# touch_glove_bullshit.net
KiCad netlist of a schematic drawn in EAGLE
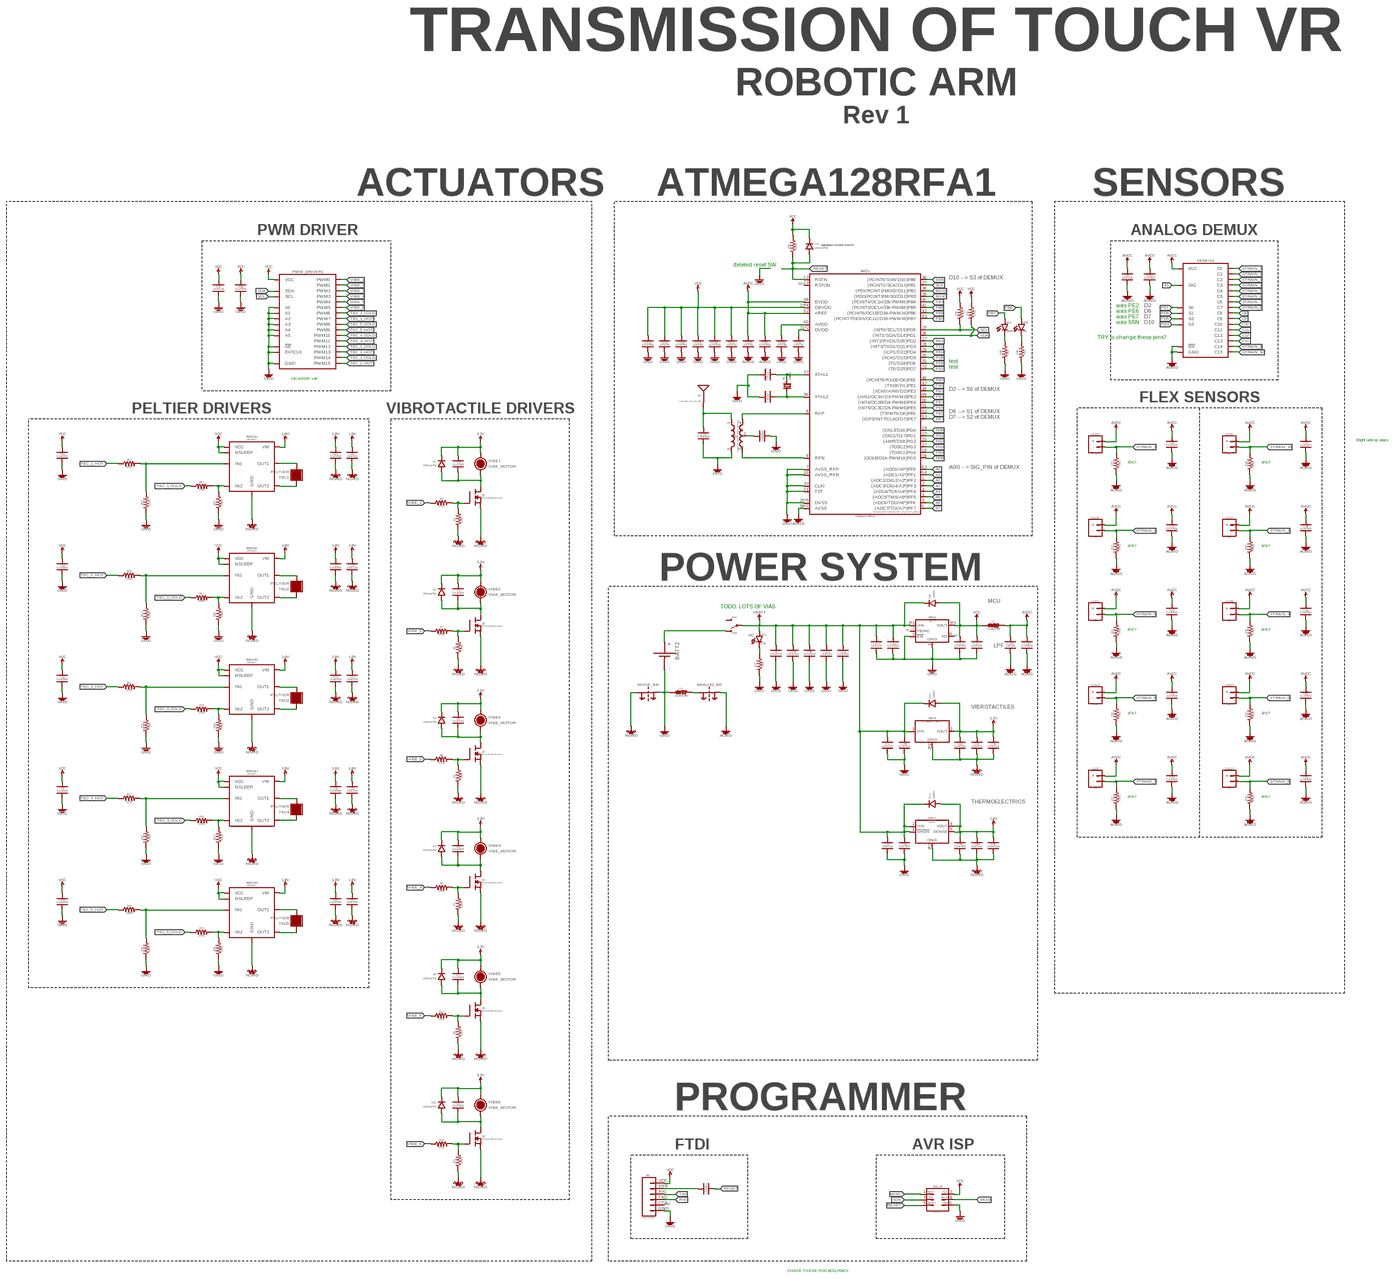
[diagram p0: schematic, sheet 1, overview]
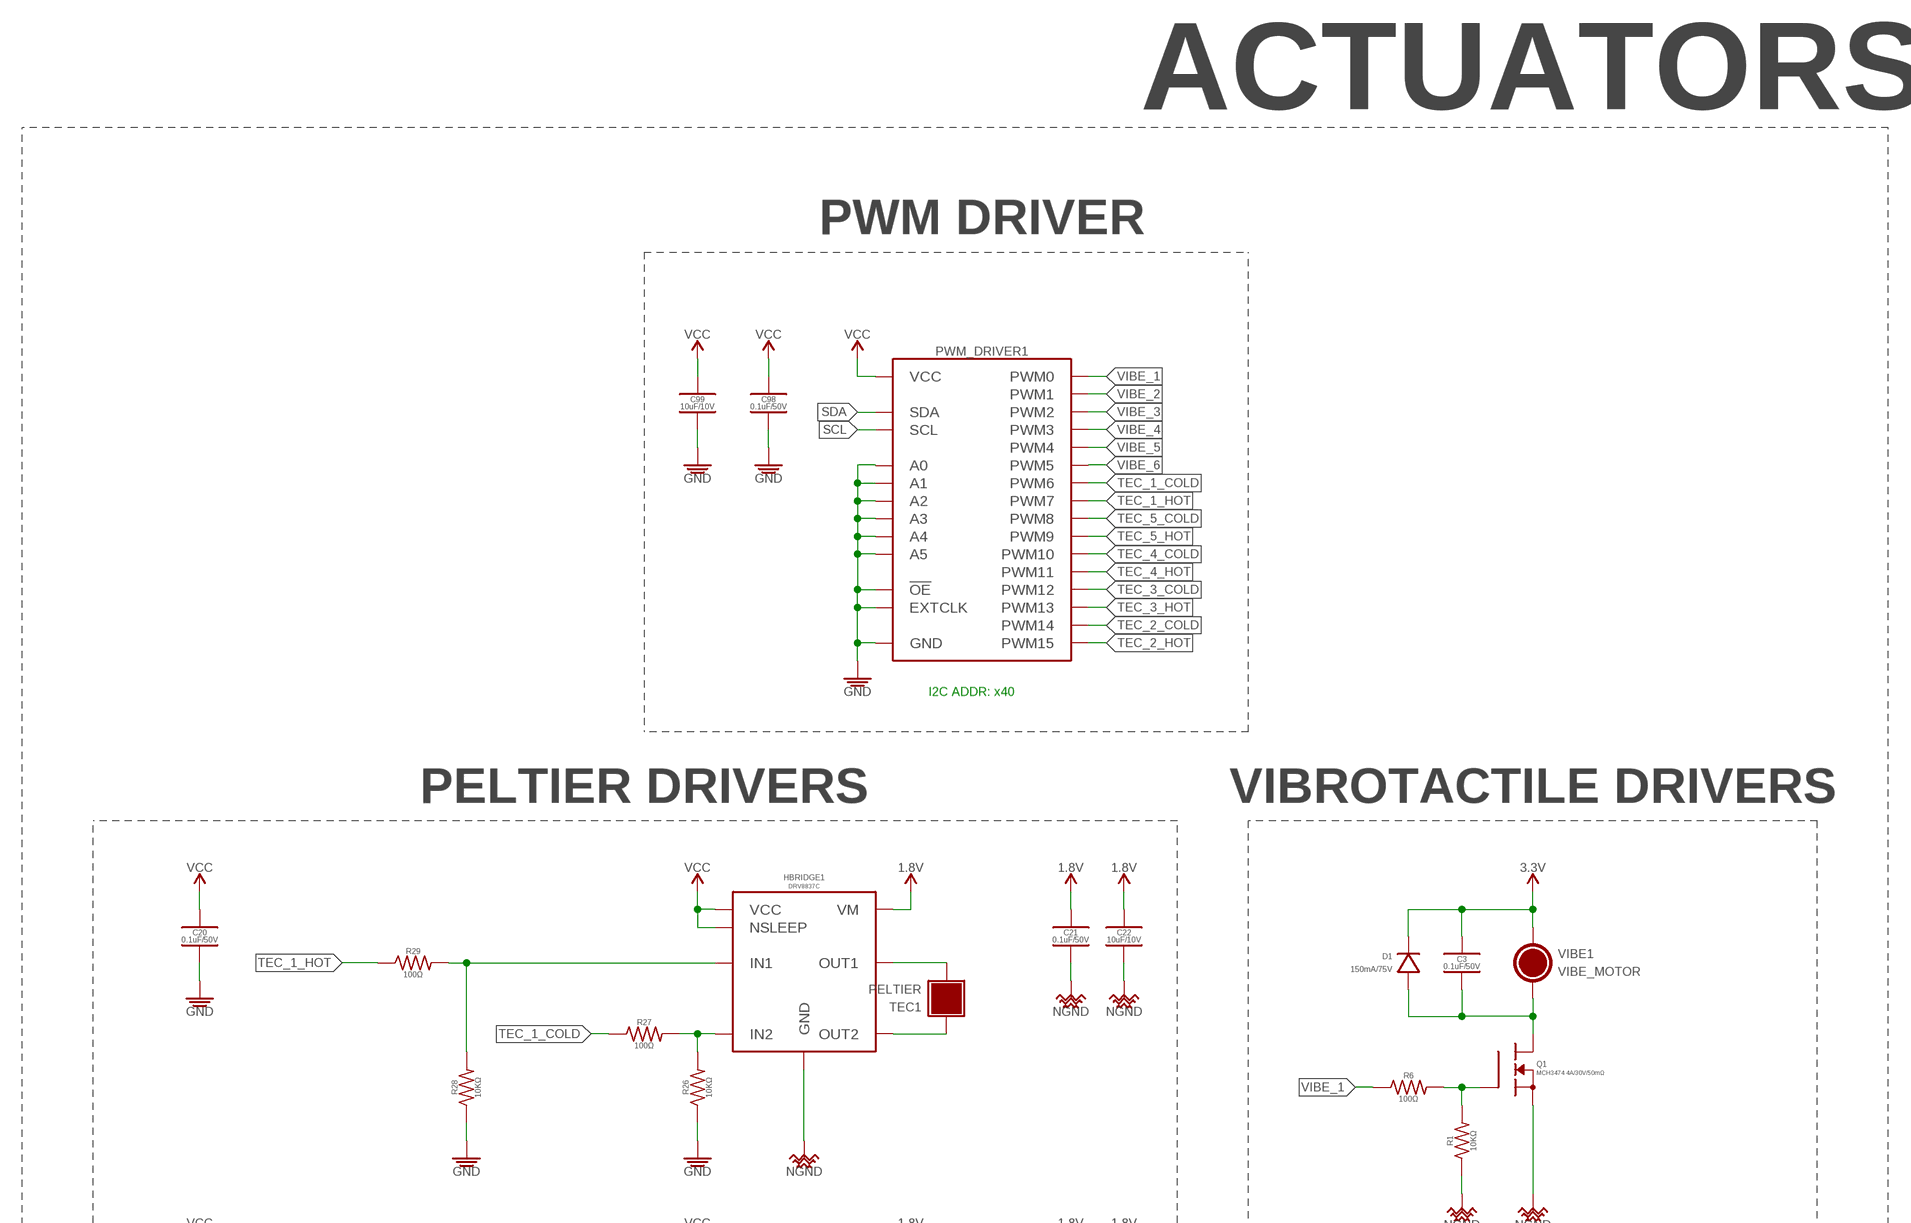
[diagram p1: schematic, sheet 1, part 1 of 4]
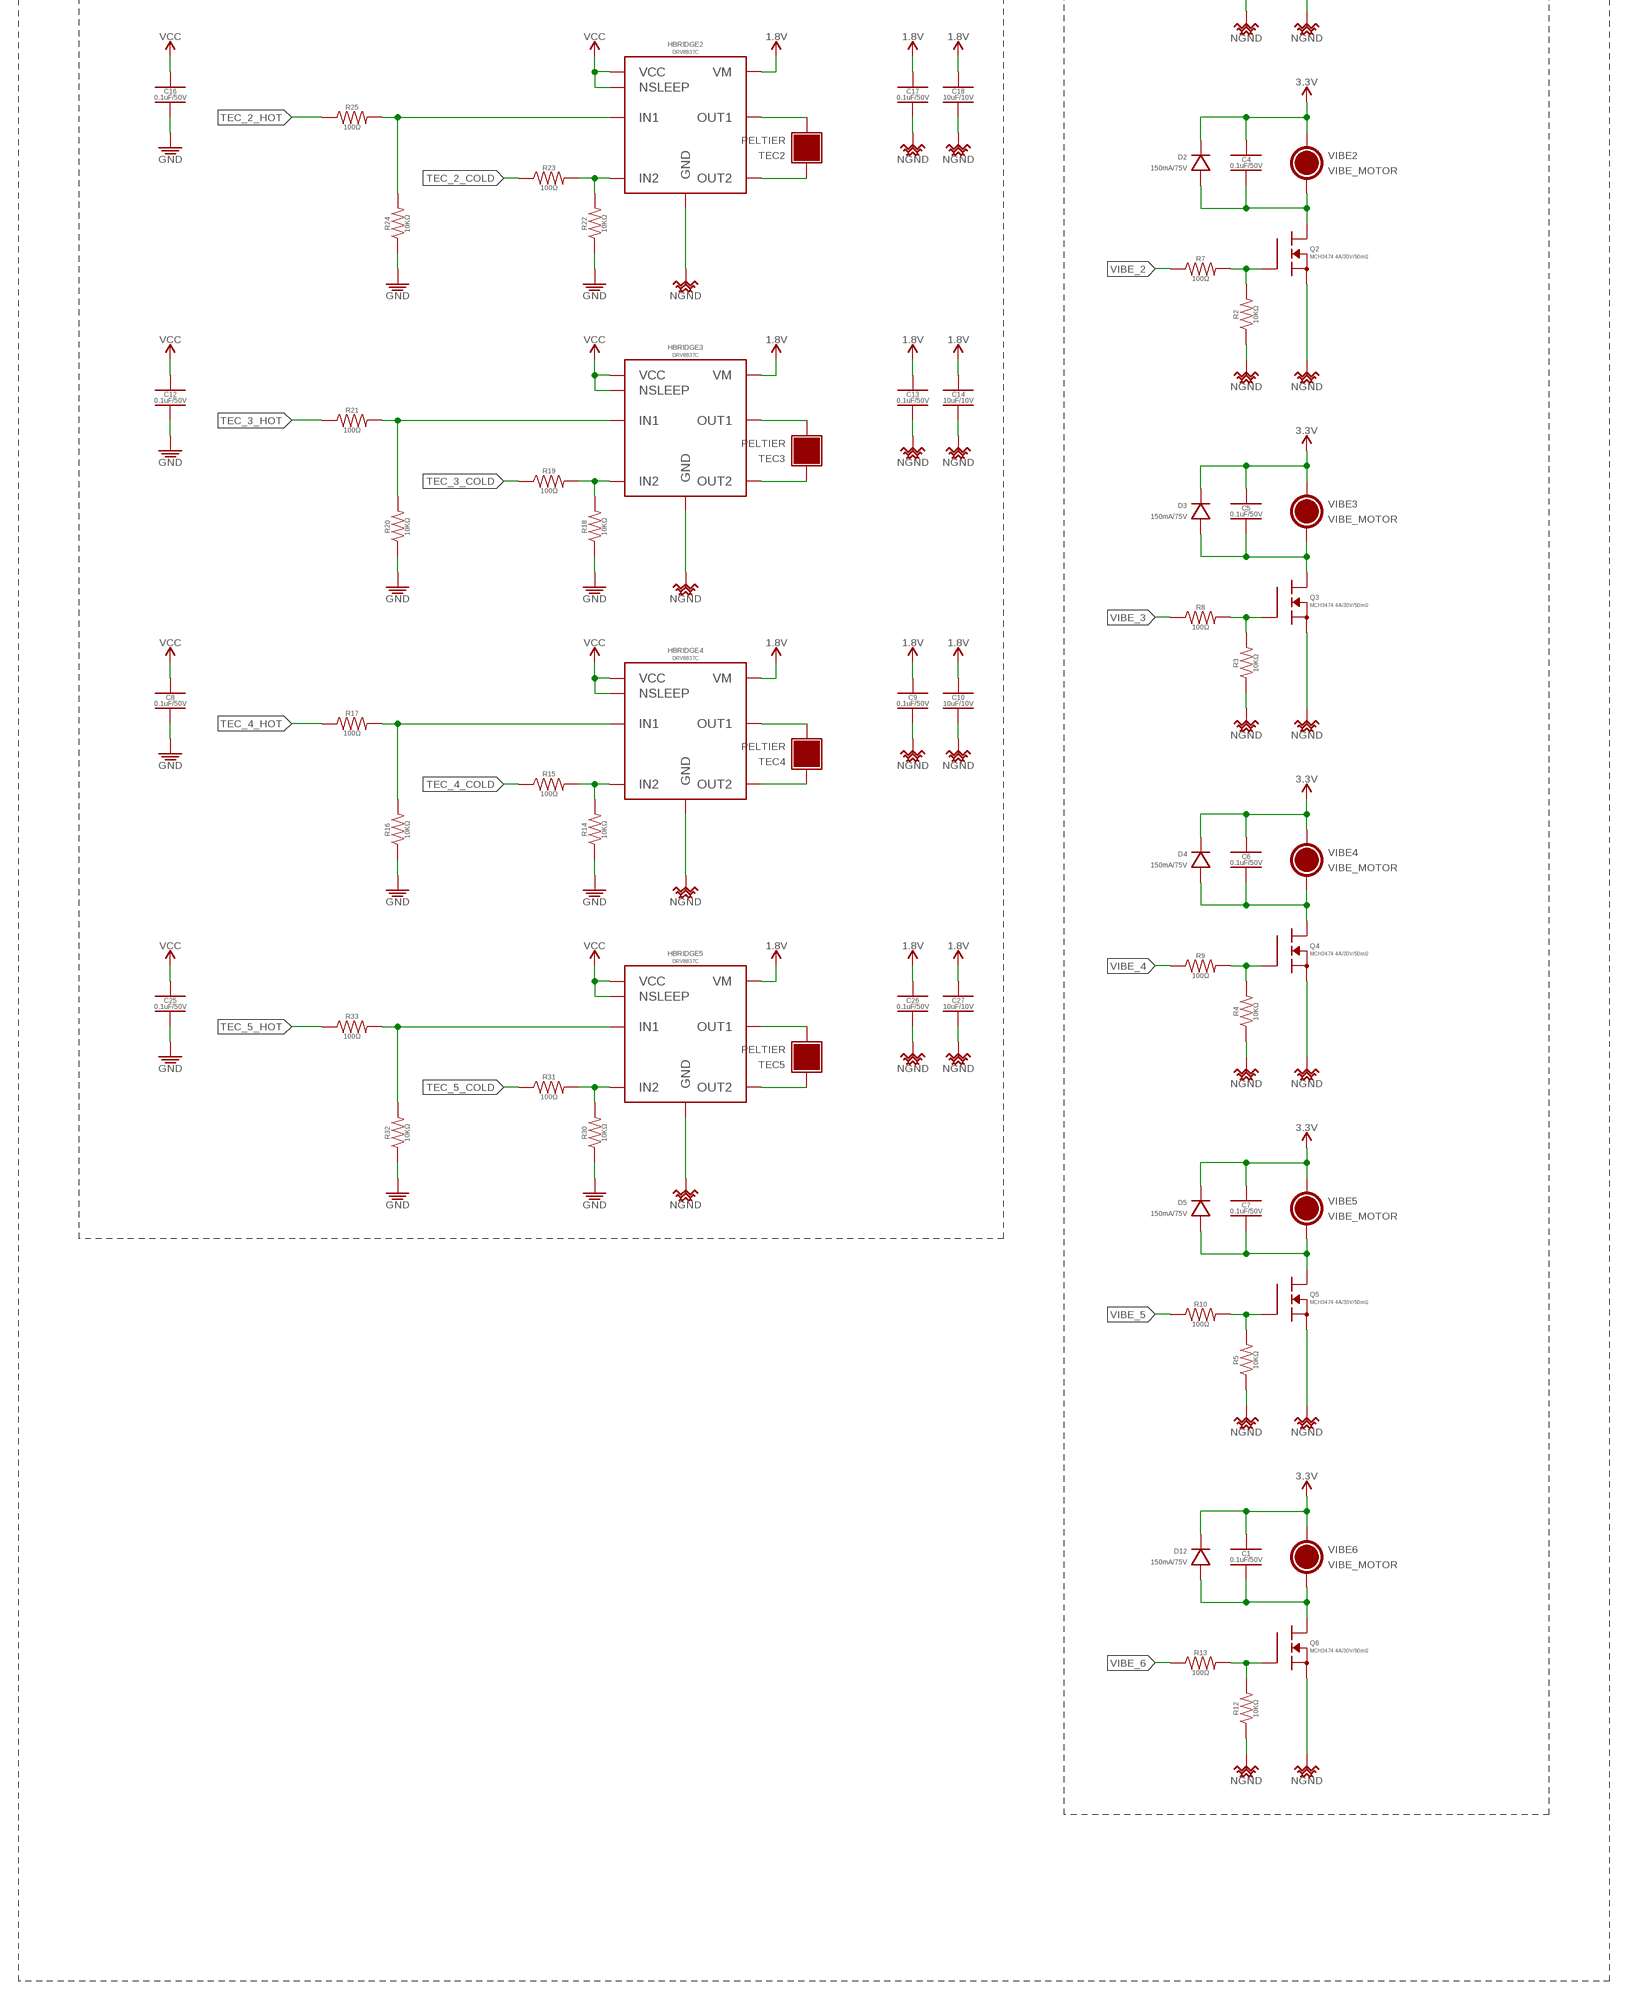
[diagram p2: schematic, sheet 1, part 2 of 4]
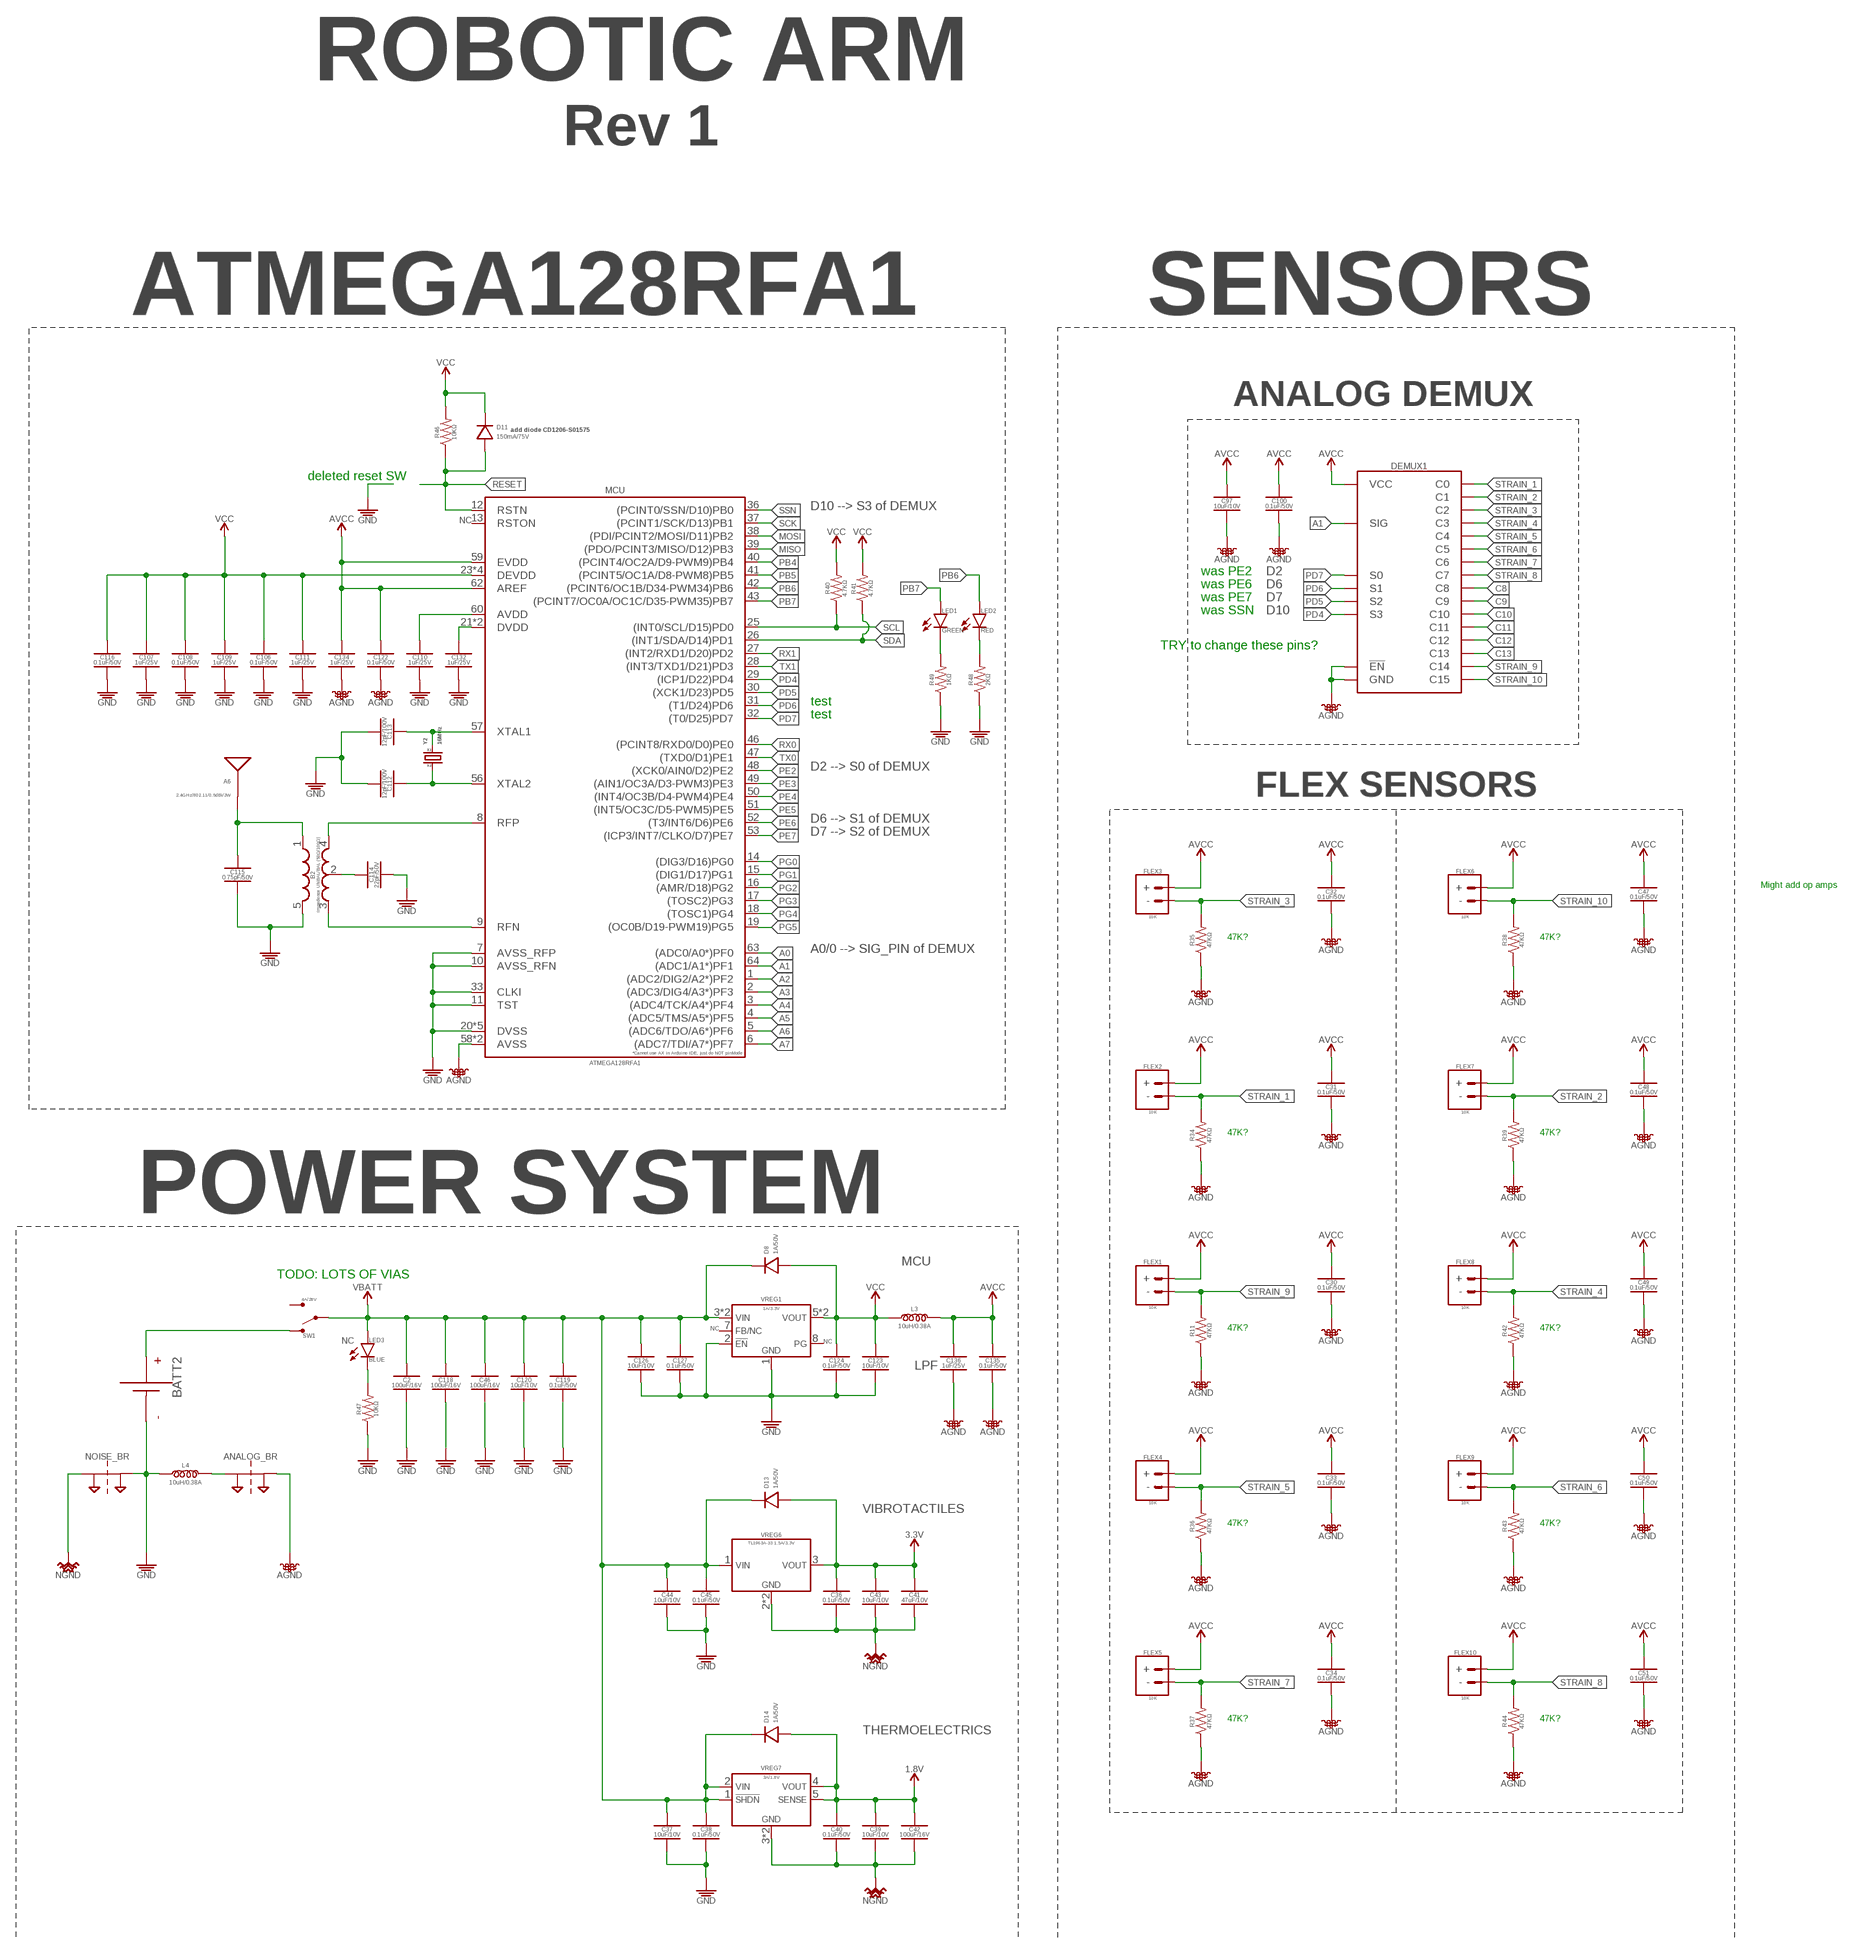
[diagram p3: schematic, sheet 1, part 3 of 4]
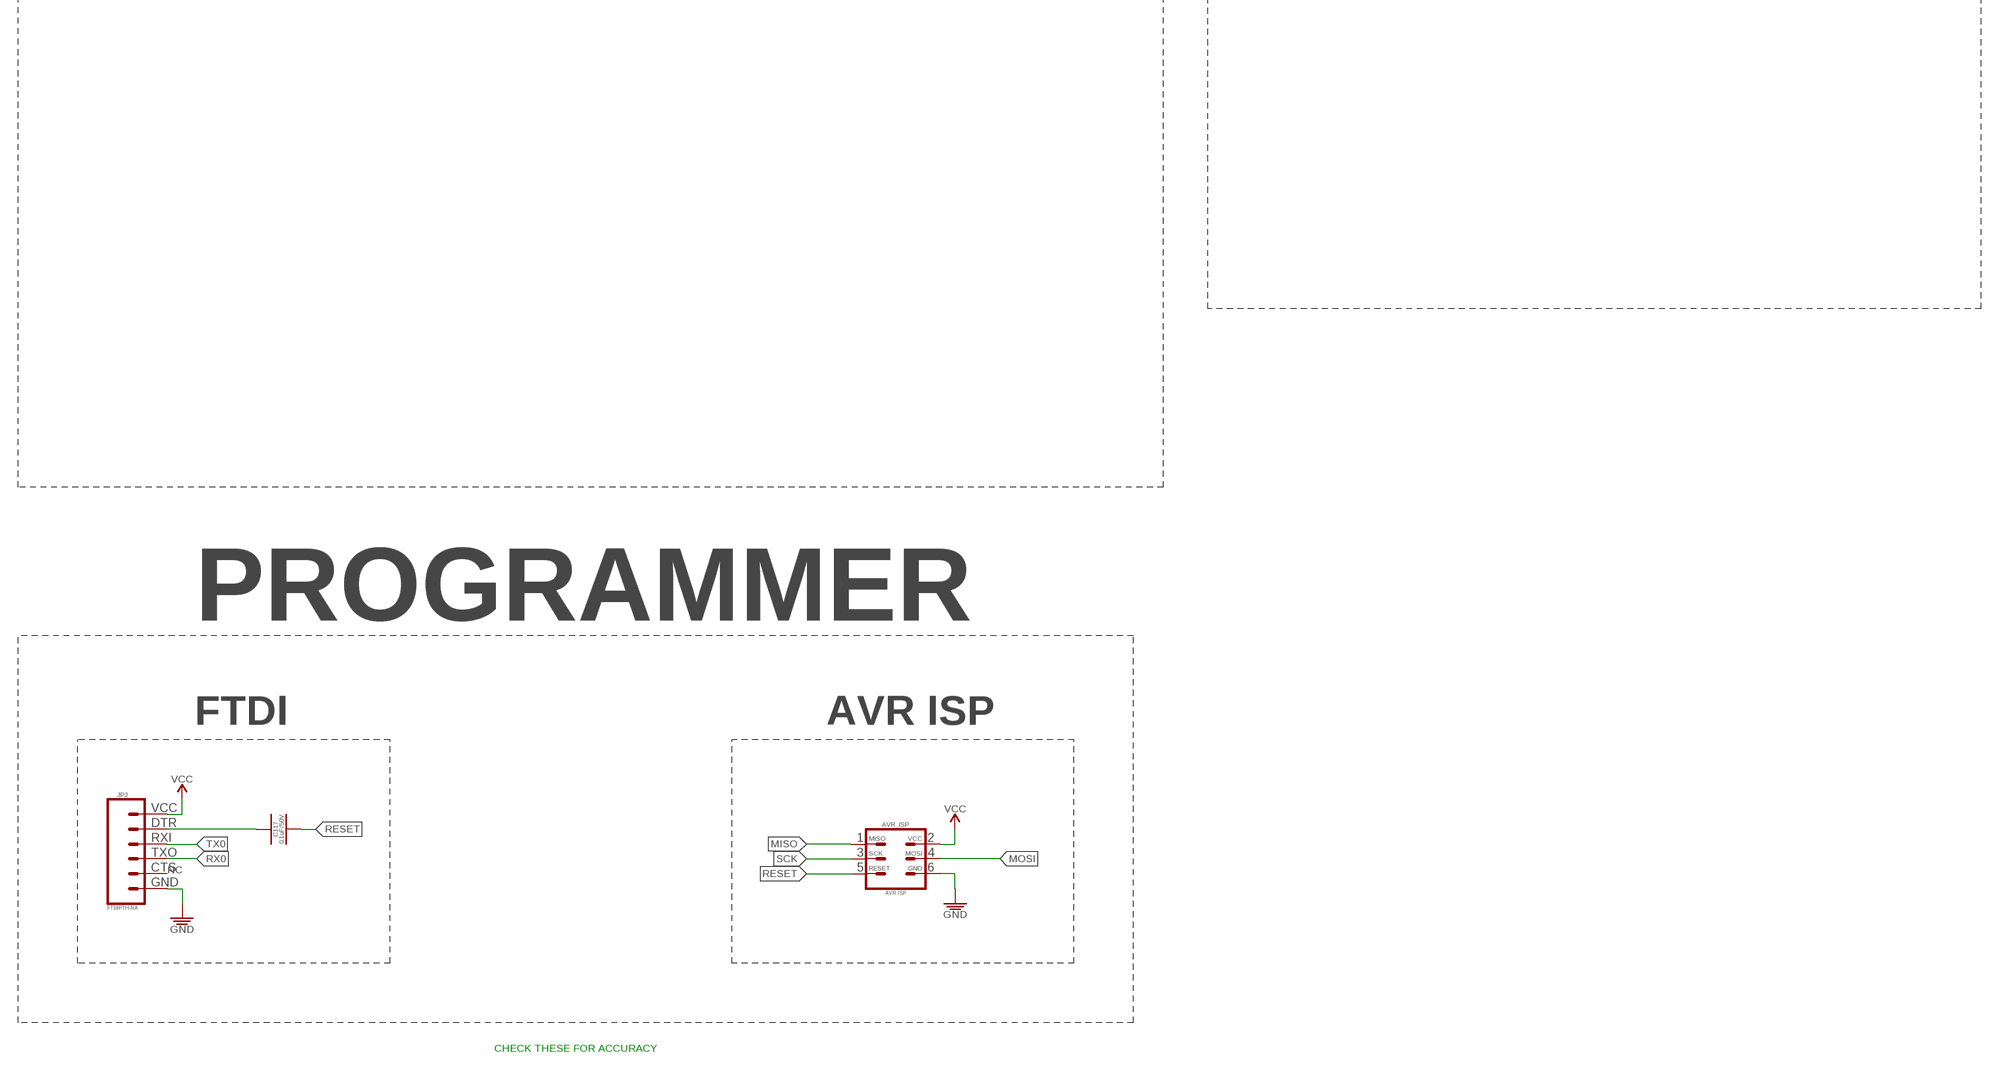
[diagram p4: schematic, sheet 1, part 4 of 4]

(export (version "E")
  (design (tool "Eeschema 10.0.6"))
  (components
    (comp (ref "A6")
      (value "2.4GHz/802.11/0.5dBi/3W")
      (footprint "eagle-import:ANTENNA-CHIP5")
      (fields
        (field (name "MFR") "Linx Technologies Inc.")
        (field (name "MPN") "ANT-2.45-CHP-T")
        (field (name "CREATOR") "Kenmei")
      )
      (libsource (lib "eagle-import") (part "ANTENNA_SMD-CHIP_2.4GHZ-0.5DBI-3W"))
    )
    (comp (ref "ANALOG_BR")
      (value "2PT_GND_TIE")
      (footprint "eagle-import:2PT_GND_TIE")
      (libsource (lib "eagle-import") (part "2PT_GND_TIE"))
    )
    (comp (ref "AVR_ISP")
      (value "AVR ISP")
      (footprint "eagle-import:2X3-NS")
      (fields (field (name "MFR") "Amphenol FCI") (field (name "MPN") "67997-206HLF"))
      (libsource (lib "eagle-import") (part "AVR_SPI_PRG_6NS"))
    )
    (comp (ref "B2")
      (value "Impedence UNBAL/BAL (50Ω/100Ω)")
      (footprint "eagle-import:0805_BALUN")
      (fields
        (field (name "MFR") "Wurth Electronics Inc")
        (field (name "MPN") "748421245")
        (field (name "CREATOR") "Kenmei")
      )
      (libsource (lib "eagle-import") (part "BALUN_SMD-0805_UNBAL/BAL-50/100"))
    )
    (comp (ref "BATT2")
      (value "BATTERYPTH_HOLES")
      (footprint "eagle-import:DUAL_PTH_PADS")
      (libsource (lib "eagle-import") (part "BATTERYPTH_HOLES"))
    )
    (comp (ref "C1")
      (value "0.1uF/50V")
      (footprint "eagle-import:_CER_SMD_0402")
      (fields
        (field (name "MFR") "Murata Electronics North America")
        (field (name "MPN") "GRM155R61H104KE19D")
        (field (name "CREATOR") "MrSwirlyEyes")
      )
      (libsource (lib "eagle-import") (part "0.1UF_SMD-0402_50V-10%"))
    )
    (comp (ref "C2")
      (value "100uF/16V")
      (footprint "eagle-import:_CER_SMD-1210")
      (fields
        (field (name "MFR") "Taiyo Yuden")
        (field (name "MPN") "EMK325ABJ107MM-T")
        (field (name "CREATOR") "MrSwirlyEyes")
      )
      (libsource (lib "eagle-import") (part "100UF_CER_SMD-1210_16V-20%"))
    )
    (comp (ref "C3")
      (value "0.1uF/50V")
      (footprint "eagle-import:_CER_SMD_0402")
      (fields
        (field (name "MFR") "Murata Electronics North America")
        (field (name "MPN") "GRM155R61H104KE19D")
        (field (name "CREATOR") "MrSwirlyEyes")
      )
      (libsource (lib "eagle-import") (part "0.1UF_SMD-0402_50V-10%"))
    )
    (comp (ref "C4")
      (value "0.1uF/50V")
      (footprint "eagle-import:_CER_SMD_0402")
      (fields
        (field (name "MFR") "Murata Electronics North America")
        (field (name "MPN") "GRM155R61H104KE19D")
        (field (name "CREATOR") "MrSwirlyEyes")
      )
      (libsource (lib "eagle-import") (part "0.1UF_SMD-0402_50V-10%"))
    )
    (comp (ref "C5")
      (value "0.1uF/50V")
      (footprint "eagle-import:_CER_SMD_0402")
      (fields
        (field (name "MFR") "Murata Electronics North America")
        (field (name "MPN") "GRM155R61H104KE19D")
        (field (name "CREATOR") "MrSwirlyEyes")
      )
      (libsource (lib "eagle-import") (part "0.1UF_SMD-0402_50V-10%"))
    )
    (comp (ref "C6")
      (value "0.1uF/50V")
      (footprint "eagle-import:_CER_SMD_0402")
      (fields
        (field (name "MFR") "Murata Electronics North America")
        (field (name "MPN") "GRM155R61H104KE19D")
        (field (name "CREATOR") "MrSwirlyEyes")
      )
      (libsource (lib "eagle-import") (part "0.1UF_SMD-0402_50V-10%"))
    )
    (comp (ref "C7")
      (value "0.1uF/50V")
      (footprint "eagle-import:_CER_SMD_0402")
      (fields
        (field (name "MFR") "Murata Electronics North America")
        (field (name "MPN") "GRM155R61H104KE19D")
        (field (name "CREATOR") "MrSwirlyEyes")
      )
      (libsource (lib "eagle-import") (part "0.1UF_SMD-0402_50V-10%"))
    )
    (comp (ref "C8")
      (value "0.1uF/50V")
      (footprint "eagle-import:_CER_SMD_0402")
      (fields
        (field (name "MFR") "Murata Electronics North America")
        (field (name "MPN") "GRM155R61H104KE19D")
        (field (name "CREATOR") "MrSwirlyEyes")
      )
      (libsource (lib "eagle-import") (part "0.1UF_SMD-0402_50V-10%"))
    )
    (comp (ref "C9")
      (value "0.1uF/50V")
      (footprint "eagle-import:_CER_SMD_0402")
      (fields
        (field (name "MFR") "Murata Electronics North America")
        (field (name "MPN") "GRM155R61H104KE19D")
        (field (name "CREATOR") "MrSwirlyEyes")
      )
      (libsource (lib "eagle-import") (part "0.1UF_SMD-0402_50V-10%"))
    )
    (comp (ref "C10")
      (value "10uF/10V")
      (footprint "eagle-import:_CER_SMD_0402")
      (fields
        (field (name "MFR") "Samsung Electro-Mechanics")
        (field (name "MPN") "CL05A106MP5NUNC")
        (field (name "CREATOR") "MrSwirlyEyes")
      )
      (libsource (lib "eagle-import") (part "10UF_CER_SMD-0402_10V-20%"))
    )
    (comp (ref "C12")
      (value "0.1uF/50V")
      (footprint "eagle-import:_CER_SMD_0402")
      (fields
        (field (name "MFR") "Murata Electronics North America")
        (field (name "MPN") "GRM155R61H104KE19D")
        (field (name "CREATOR") "MrSwirlyEyes")
      )
      (libsource (lib "eagle-import") (part "0.1UF_SMD-0402_50V-10%"))
    )
    (comp (ref "C13")
      (value "0.1uF/50V")
      (footprint "eagle-import:_CER_SMD_0402")
      (fields
        (field (name "MFR") "Murata Electronics North America")
        (field (name "MPN") "GRM155R61H104KE19D")
        (field (name "CREATOR") "MrSwirlyEyes")
      )
      (libsource (lib "eagle-import") (part "0.1UF_SMD-0402_50V-10%"))
    )
    (comp (ref "C14")
      (value "10uF/10V")
      (footprint "eagle-import:_CER_SMD_0402")
      (fields
        (field (name "MFR") "Samsung Electro-Mechanics")
        (field (name "MPN") "CL05A106MP5NUNC")
        (field (name "CREATOR") "MrSwirlyEyes")
      )
      (libsource (lib "eagle-import") (part "10UF_CER_SMD-0402_10V-20%"))
    )
    (comp (ref "C16")
      (value "0.1uF/50V")
      (footprint "eagle-import:_CER_SMD_0402")
      (fields
        (field (name "MFR") "Murata Electronics North America")
        (field (name "MPN") "GRM155R61H104KE19D")
        (field (name "CREATOR") "MrSwirlyEyes")
      )
      (libsource (lib "eagle-import") (part "0.1UF_SMD-0402_50V-10%"))
    )
    (comp (ref "C17")
      (value "0.1uF/50V")
      (footprint "eagle-import:_CER_SMD_0402")
      (fields
        (field (name "MFR") "Murata Electronics North America")
        (field (name "MPN") "GRM155R61H104KE19D")
        (field (name "CREATOR") "MrSwirlyEyes")
      )
      (libsource (lib "eagle-import") (part "0.1UF_SMD-0402_50V-10%"))
    )
    (comp (ref "C18")
      (value "10uF/10V")
      (footprint "eagle-import:_CER_SMD_0402")
      (fields
        (field (name "MFR") "Samsung Electro-Mechanics")
        (field (name "MPN") "CL05A106MP5NUNC")
        (field (name "CREATOR") "MrSwirlyEyes")
      )
      (libsource (lib "eagle-import") (part "10UF_CER_SMD-0402_10V-20%"))
    )
    (comp (ref "C20")
      (value "0.1uF/50V")
      (footprint "eagle-import:_CER_SMD_0402")
      (fields
        (field (name "MFR") "Murata Electronics North America")
        (field (name "MPN") "GRM155R61H104KE19D")
        (field (name "CREATOR") "MrSwirlyEyes")
      )
      (libsource (lib "eagle-import") (part "0.1UF_SMD-0402_50V-10%"))
    )
    (comp (ref "C21")
      (value "0.1uF/50V")
      (footprint "eagle-import:_CER_SMD_0402")
      (fields
        (field (name "MFR") "Murata Electronics North America")
        (field (name "MPN") "GRM155R61H104KE19D")
        (field (name "CREATOR") "MrSwirlyEyes")
      )
      (libsource (lib "eagle-import") (part "0.1UF_SMD-0402_50V-10%"))
    )
    (comp (ref "C22")
      (value "10uF/10V")
      (footprint "eagle-import:_CER_SMD_0402")
      (fields
        (field (name "MFR") "Samsung Electro-Mechanics")
        (field (name "MPN") "CL05A106MP5NUNC")
        (field (name "CREATOR") "MrSwirlyEyes")
      )
      (libsource (lib "eagle-import") (part "10UF_CER_SMD-0402_10V-20%"))
    )
    (comp (ref "C25")
      (value "0.1uF/50V")
      (footprint "eagle-import:_CER_SMD_0402")
      (fields
        (field (name "MFR") "Murata Electronics North America")
        (field (name "MPN") "GRM155R61H104KE19D")
        (field (name "CREATOR") "MrSwirlyEyes")
      )
      (libsource (lib "eagle-import") (part "0.1UF_SMD-0402_50V-10%"))
    )
    (comp (ref "C26")
      (value "0.1uF/50V")
      (footprint "eagle-import:_CER_SMD_0402")
      (fields
        (field (name "MFR") "Murata Electronics North America")
        (field (name "MPN") "GRM155R61H104KE19D")
        (field (name "CREATOR") "MrSwirlyEyes")
      )
      (libsource (lib "eagle-import") (part "0.1UF_SMD-0402_50V-10%"))
    )
    (comp (ref "C27")
      (value "10uF/10V")
      (footprint "eagle-import:_CER_SMD_0402")
      (fields
        (field (name "MFR") "Samsung Electro-Mechanics")
        (field (name "MPN") "CL05A106MP5NUNC")
        (field (name "CREATOR") "MrSwirlyEyes")
      )
      (libsource (lib "eagle-import") (part "10UF_CER_SMD-0402_10V-20%"))
    )
    (comp (ref "C30")
      (value "0.1uF/50V")
      (footprint "eagle-import:_CER_SMD_0402")
      (fields
        (field (name "MFR") "Murata Electronics North America")
        (field (name "MPN") "GRM155R61H104KE19D")
        (field (name "CREATOR") "MrSwirlyEyes")
      )
      (libsource (lib "eagle-import") (part "0.1UF_SMD-0402_50V-10%"))
    )
    (comp (ref "C31")
      (value "0.1uF/50V")
      (footprint "eagle-import:_CER_SMD_0402")
      (fields
        (field (name "MFR") "Murata Electronics North America")
        (field (name "MPN") "GRM155R61H104KE19D")
        (field (name "CREATOR") "MrSwirlyEyes")
      )
      (libsource (lib "eagle-import") (part "0.1UF_SMD-0402_50V-10%"))
    )
    (comp (ref "C32")
      (value "0.1uF/50V")
      (footprint "eagle-import:_CER_SMD_0402")
      (fields
        (field (name "MFR") "Murata Electronics North America")
        (field (name "MPN") "GRM155R61H104KE19D")
        (field (name "CREATOR") "MrSwirlyEyes")
      )
      (libsource (lib "eagle-import") (part "0.1UF_SMD-0402_50V-10%"))
    )
    (comp (ref "C33")
      (value "0.1uF/50V")
      (footprint "eagle-import:_CER_SMD_0402")
      (fields
        (field (name "MFR") "Murata Electronics North America")
        (field (name "MPN") "GRM155R61H104KE19D")
        (field (name "CREATOR") "MrSwirlyEyes")
      )
      (libsource (lib "eagle-import") (part "0.1UF_SMD-0402_50V-10%"))
    )
    (comp (ref "C34")
      (value "0.1uF/50V")
      (footprint "eagle-import:_CER_SMD_0402")
      (fields
        (field (name "MFR") "Murata Electronics North America")
        (field (name "MPN") "GRM155R61H104KE19D")
        (field (name "CREATOR") "MrSwirlyEyes")
      )
      (libsource (lib "eagle-import") (part "0.1UF_SMD-0402_50V-10%"))
    )
    (comp (ref "C36")
      (value "0.1uF/50V")
      (footprint "eagle-import:_CER_SMD_0402")
      (fields
        (field (name "MFR") "Murata Electronics North America")
        (field (name "MPN") "GRM155R61H104KE19D")
        (field (name "CREATOR") "MrSwirlyEyes")
      )
      (libsource (lib "eagle-import") (part "0.1UF_SMD-0402_50V-10%"))
    )
    (comp (ref "C37")
      (value "10uF/10V")
      (footprint "eagle-import:_CER_SMD_0402")
      (fields
        (field (name "MFR") "Samsung Electro-Mechanics")
        (field (name "MPN") "CL05A106MP5NUNC")
        (field (name "CREATOR") "MrSwirlyEyes")
      )
      (libsource (lib "eagle-import") (part "10UF_CER_SMD-0402_10V-20%"))
    )
    (comp (ref "C38")
      (value "0.1uF/50V")
      (footprint "eagle-import:_CER_SMD_0402")
      (fields
        (field (name "MFR") "Murata Electronics North America")
        (field (name "MPN") "GRM155R61H104KE19D")
        (field (name "CREATOR") "MrSwirlyEyes")
      )
      (libsource (lib "eagle-import") (part "0.1UF_SMD-0402_50V-10%"))
    )
    (comp (ref "C39")
      (value "10uF/10V")
      (footprint "eagle-import:_CER_SMD_0402")
      (fields
        (field (name "MFR") "Samsung Electro-Mechanics")
        (field (name "MPN") "CL05A106MP5NUNC")
        (field (name "CREATOR") "MrSwirlyEyes")
      )
      (libsource (lib "eagle-import") (part "10UF_CER_SMD-0402_10V-20%"))
    )
    (comp (ref "C40")
      (value "0.1uF/50V")
      (footprint "eagle-import:_CER_SMD_0402")
      (fields
        (field (name "MFR") "Murata Electronics North America")
        (field (name "MPN") "GRM155R61H104KE19D")
        (field (name "CREATOR") "MrSwirlyEyes")
      )
      (libsource (lib "eagle-import") (part "0.1UF_SMD-0402_50V-10%"))
    )
    (comp (ref "C41")
      (value "47uF/10V")
      (footprint "eagle-import:_CER_SMD-805")
      (fields
        (field (name "MFR") "Murata Electronics North America")
        (field (name "MPN") "GRM21BR61A476ME15L")
        (field (name "CREATOR") "MrSwirlyEyes")
      )
      (libsource (lib "eagle-import") (part "47UF_CER_SMD-0805_10V-20%"))
    )
    (comp (ref "C42")
      (value "100uF/16V")
      (footprint "eagle-import:_CER_SMD-1210")
      (fields
        (field (name "MFR") "Taiyo Yuden")
        (field (name "MPN") "EMK325ABJ107MM-T")
        (field (name "CREATOR") "MrSwirlyEyes")
      )
      (libsource (lib "eagle-import") (part "100UF_CER_SMD-1210_16V-20%"))
    )
    (comp (ref "C43")
      (value "10uF/10V")
      (footprint "eagle-import:_CER_SMD_0402")
      (fields
        (field (name "MFR") "Samsung Electro-Mechanics")
        (field (name "MPN") "CL05A106MP5NUNC")
        (field (name "CREATOR") "MrSwirlyEyes")
      )
      (libsource (lib "eagle-import") (part "10UF_CER_SMD-0402_10V-20%"))
    )
    (comp (ref "C44")
      (value "10uF/10V")
      (footprint "eagle-import:_CER_SMD_0402")
      (fields
        (field (name "MFR") "Samsung Electro-Mechanics")
        (field (name "MPN") "CL05A106MP5NUNC")
        (field (name "CREATOR") "MrSwirlyEyes")
      )
      (libsource (lib "eagle-import") (part "10UF_CER_SMD-0402_10V-20%"))
    )
    (comp (ref "C45")
      (value "0.1uF/50V")
      (footprint "eagle-import:_CER_SMD_0402")
      (fields
        (field (name "MFR") "Murata Electronics North America")
        (field (name "MPN") "GRM155R61H104KE19D")
        (field (name "CREATOR") "MrSwirlyEyes")
      )
      (libsource (lib "eagle-import") (part "0.1UF_SMD-0402_50V-10%"))
    )
    (comp (ref "C46")
      (value "100uF/16V")
      (footprint "eagle-import:_CER_SMD-1210")
      (fields
        (field (name "MFR") "Taiyo Yuden")
        (field (name "MPN") "EMK325ABJ107MM-T")
        (field (name "CREATOR") "MrSwirlyEyes")
      )
      (libsource (lib "eagle-import") (part "100UF_CER_SMD-1210_16V-20%"))
    )
    (comp (ref "C47")
      (value "0.1uF/50V")
      (footprint "eagle-import:_CER_SMD_0402")
      (fields
        (field (name "MFR") "Murata Electronics North America")
        (field (name "MPN") "GRM155R61H104KE19D")
        (field (name "CREATOR") "MrSwirlyEyes")
      )
      (libsource (lib "eagle-import") (part "0.1UF_SMD-0402_50V-10%"))
    )
    (comp (ref "C48")
      (value "0.1uF/50V")
      (footprint "eagle-import:_CER_SMD_0402")
      (fields
        (field (name "MFR") "Murata Electronics North America")
        (field (name "MPN") "GRM155R61H104KE19D")
        (field (name "CREATOR") "MrSwirlyEyes")
      )
      (libsource (lib "eagle-import") (part "0.1UF_SMD-0402_50V-10%"))
    )
    (comp (ref "C49")
      (value "0.1uF/50V")
      (footprint "eagle-import:_CER_SMD_0402")
      (fields
        (field (name "MFR") "Murata Electronics North America")
        (field (name "MPN") "GRM155R61H104KE19D")
        (field (name "CREATOR") "MrSwirlyEyes")
      )
      (libsource (lib "eagle-import") (part "0.1UF_SMD-0402_50V-10%"))
    )
    (comp (ref "C50")
      (value "0.1uF/50V")
      (footprint "eagle-import:_CER_SMD_0402")
      (fields
        (field (name "MFR") "Murata Electronics North America")
        (field (name "MPN") "GRM155R61H104KE19D")
        (field (name "CREATOR") "MrSwirlyEyes")
      )
      (libsource (lib "eagle-import") (part "0.1UF_SMD-0402_50V-10%"))
    )
    (comp (ref "C51")
      (value "0.1uF/50V")
      (footprint "eagle-import:_CER_SMD_0402")
      (fields
        (field (name "MFR") "Murata Electronics North America")
        (field (name "MPN") "GRM155R61H104KE19D")
        (field (name "CREATOR") "MrSwirlyEyes")
      )
      (libsource (lib "eagle-import") (part "0.1UF_SMD-0402_50V-10%"))
    )
    (comp (ref "C97")
      (value "10uF/10V")
      (footprint "eagle-import:_CER_SMD_0402")
      (fields
        (field (name "MFR") "Samsung Electro-Mechanics")
        (field (name "MPN") "CL05A106MP5NUNC")
        (field (name "CREATOR") "MrSwirlyEyes")
      )
      (libsource (lib "eagle-import") (part "10UF_CER_SMD-0402_10V-20%"))
    )
    (comp (ref "C98")
      (value "0.1uF/50V")
      (footprint "eagle-import:_CER_SMD_0402")
      (fields
        (field (name "MFR") "Murata Electronics North America")
        (field (name "MPN") "GRM155R61H104KE19D")
        (field (name "CREATOR") "MrSwirlyEyes")
      )
      (libsource (lib "eagle-import") (part "0.1UF_SMD-0402_50V-10%"))
    )
    (comp (ref "C99")
      (value "10uF/10V")
      (footprint "eagle-import:_CER_SMD_0402")
      (fields
        (field (name "MFR") "Samsung Electro-Mechanics")
        (field (name "MPN") "CL05A106MP5NUNC")
        (field (name "CREATOR") "MrSwirlyEyes")
      )
      (libsource (lib "eagle-import") (part "10UF_CER_SMD-0402_10V-20%"))
    )
    (comp (ref "C100")
      (value "0.1uF/50V")
      (footprint "eagle-import:_CER_SMD_0402")
      (fields
        (field (name "MFR") "Murata Electronics North America")
        (field (name "MPN") "GRM155R61H104KE19D")
        (field (name "CREATOR") "MrSwirlyEyes")
      )
      (libsource (lib "eagle-import") (part "0.1UF_SMD-0402_50V-10%"))
    )
    (comp (ref "C106")
      (value "0.1uF/50V")
      (footprint "eagle-import:_CER_SMD_0402")
      (fields
        (field (name "MFR") "Murata Electronics North America")
        (field (name "MPN") "GRM155R61H104KE19D")
        (field (name "CREATOR") "MrSwirlyEyes")
      )
      (libsource (lib "eagle-import") (part "0.1UF_SMD-0402_50V-10%"))
    )
    (comp (ref "C107")
      (value "1uF/25V")
      (footprint "eagle-import:_CER_SMD_0402")
      (fields
        (field (name "MFR") "Murata Electronics North America")
        (field (name "MPN") "GRM155C81E105KE11D")
        (field (name "CREATOR") "MrSwirlyEyes")
      )
      (libsource (lib "eagle-import") (part "1UF_CER_SMD-0402_25V-10%"))
    )
    (comp (ref "C108")
      (value "0.1uF/50V")
      (footprint "eagle-import:_CER_SMD_0402")
      (fields
        (field (name "MFR") "Murata Electronics North America")
        (field (name "MPN") "GRM155R61H104KE19D")
        (field (name "CREATOR") "MrSwirlyEyes")
      )
      (libsource (lib "eagle-import") (part "0.1UF_SMD-0402_50V-10%"))
    )
    (comp (ref "C109")
      (value "1uF/25V")
      (footprint "eagle-import:_CER_SMD_0402")
      (fields
        (field (name "MFR") "Murata Electronics North America")
        (field (name "MPN") "GRM155C81E105KE11D")
        (field (name "CREATOR") "MrSwirlyEyes")
      )
      (libsource (lib "eagle-import") (part "1UF_CER_SMD-0402_25V-10%"))
    )
    (comp (ref "C110")
      (value "1uF/25V")
      (footprint "eagle-import:_CER_SMD_0402")
      (fields
        (field (name "MFR") "Murata Electronics North America")
        (field (name "MPN") "GRM155C81E105KE11D")
        (field (name "CREATOR") "MrSwirlyEyes")
      )
      (libsource (lib "eagle-import") (part "1UF_CER_SMD-0402_25V-10%"))
    )
    (comp (ref "C111")
      (value "1uF/25V")
      (footprint "eagle-import:_CER_SMD_0402")
      (fields
        (field (name "MFR") "Murata Electronics North America")
        (field (name "MPN") "GRM155C81E105KE11D")
        (field (name "CREATOR") "MrSwirlyEyes")
      )
      (libsource (lib "eagle-import") (part "1UF_CER_SMD-0402_25V-10%"))
    )
    (comp (ref "C112")
      (value "12pF/100V")
      (footprint "eagle-import:_CER_SMD_0402")
      (fields
        (field (name "MFR") "Murata Electronics North America")
        (field (name "MPN") "GRM1555C2A120JA01D")
        (field (name "CREATOR") "MrSwirlyEyes")
      )
      (libsource (lib "eagle-import") (part "12PF_SMD-0402_100V-5%"))
    )
    (comp (ref "C113")
      (value "12pF/100V")
      (footprint "eagle-import:_CER_SMD_0402")
      (fields
        (field (name "MFR") "Murata Electronics North America")
        (field (name "MPN") "GRM1555C2A120JA01D")
        (field (name "CREATOR") "MrSwirlyEyes")
      )
      (libsource (lib "eagle-import") (part "12PF_SMD-0402_100V-5%"))
    )
    (comp (ref "C114")
      (value "22pF/50V")
      (footprint "eagle-import:_CER_SMD_0402")
      (fields
        (field (name "MFR") "Murata Electronics North America")
        (field (name "MPN") "GRM1555C1H220JA01D")
        (field (name "CREATOR") "MrSwirlyEyes")
      )
      (libsource (lib "eagle-import") (part "22PF_SMD-0402_100V-5%"))
    )
    (comp (ref "C115")
      (value "0.75pF/50V")
      (footprint "eagle-import:_CER_SMD_0402")
      (fields
        (field (name "MFR") "Murata Electronics North America")
        (field (name "MPN") "GRM1555C1HR75CA01D")
        (field (name "CREATOR") "MrSwirlyEyes")
      )
      (libsource (lib "eagle-import") (part "0.75PF_SMD-0402_50V-33%"))
    )
    (comp (ref "C116")
      (value "0.1uF/50V")
      (footprint "eagle-import:_CER_SMD_0402")
      (fields
        (field (name "MFR") "Murata Electronics North America")
        (field (name "MPN") "GRM155R61H104KE19D")
        (field (name "CREATOR") "MrSwirlyEyes")
      )
      (libsource (lib "eagle-import") (part "0.1UF_SMD-0402_50V-10%"))
    )
    (comp (ref "C117")
      (value "0.1uF/50V")
      (footprint "eagle-import:_CER_SMD_0402")
      (fields
        (field (name "MFR") "Murata Electronics North America")
        (field (name "MPN") "GRM155R61H104KE19D")
        (field (name "CREATOR") "MrSwirlyEyes")
      )
      (libsource (lib "eagle-import") (part "0.1UF_SMD-0402_50V-10%"))
    )
    (comp (ref "C118")
      (value "100uF/16V")
      (footprint "eagle-import:_CER_SMD-1210")
      (fields
        (field (name "MFR") "Taiyo Yuden")
        (field (name "MPN") "EMK325ABJ107MM-T")
        (field (name "CREATOR") "MrSwirlyEyes")
      )
      (libsource (lib "eagle-import") (part "100UF_CER_SMD-1210_16V-20%"))
    )
    (comp (ref "C119")
      (value "0.1uF/50V")
      (footprint "eagle-import:_CER_SMD_0402")
      (fields
        (field (name "MFR") "Murata Electronics North America")
        (field (name "MPN") "GRM155R61H104KE19D")
        (field (name "CREATOR") "MrSwirlyEyes")
      )
      (libsource (lib "eagle-import") (part "0.1UF_SMD-0402_50V-10%"))
    )
    (comp (ref "C120")
      (value "10uF/10V")
      (footprint "eagle-import:_CER_SMD_0402")
      (fields
        (field (name "MFR") "Samsung Electro-Mechanics")
        (field (name "MPN") "CL05A106MP5NUNC")
        (field (name "CREATOR") "MrSwirlyEyes")
      )
      (libsource (lib "eagle-import") (part "10UF_CER_SMD-0402_10V-20%"))
    )
    (comp (ref "C122")
      (value "0.1uF/50V")
      (footprint "eagle-import:_CER_SMD_0402")
      (fields
        (field (name "MFR") "Murata Electronics North America")
        (field (name "MPN") "GRM155R61H104KE19D")
        (field (name "CREATOR") "MrSwirlyEyes")
      )
      (libsource (lib "eagle-import") (part "0.1UF_SMD-0402_50V-10%"))
    )
    (comp (ref "C123")
      (value "10uF/10V")
      (footprint "eagle-import:_CER_SMD_0402")
      (fields
        (field (name "MFR") "Samsung Electro-Mechanics")
        (field (name "MPN") "CL05A106MP5NUNC")
        (field (name "CREATOR") "MrSwirlyEyes")
      )
      (libsource (lib "eagle-import") (part "10UF_CER_SMD-0402_10V-20%"))
    )
    (comp (ref "C124")
      (value "0.1uF/50V")
      (footprint "eagle-import:_CER_SMD_0402")
      (fields
        (field (name "MFR") "Murata Electronics North America")
        (field (name "MPN") "GRM155R61H104KE19D")
        (field (name "CREATOR") "MrSwirlyEyes")
      )
      (libsource (lib "eagle-import") (part "0.1UF_SMD-0402_50V-10%"))
    )
    (comp (ref "C126")
      (value "10uF/10V")
      (footprint "eagle-import:_CER_SMD_0402")
      (fields
        (field (name "MFR") "Samsung Electro-Mechanics")
        (field (name "MPN") "CL05A106MP5NUNC")
        (field (name "CREATOR") "MrSwirlyEyes")
      )
      (libsource (lib "eagle-import") (part "10UF_CER_SMD-0402_10V-20%"))
    )
    (comp (ref "C127")
      (value "0.1uF/50V")
      (footprint "eagle-import:_CER_SMD_0402")
      (fields
        (field (name "MFR") "Murata Electronics North America")
        (field (name "MPN") "GRM155R61H104KE19D")
        (field (name "CREATOR") "MrSwirlyEyes")
      )
      (libsource (lib "eagle-import") (part "0.1UF_SMD-0402_50V-10%"))
    )
    (comp (ref "C132")
      (value "1uF/25V")
      (footprint "eagle-import:_CER_SMD_0402")
      (fields
        (field (name "MFR") "Murata Electronics North America")
        (field (name "MPN") "GRM155C81E105KE11D")
        (field (name "CREATOR") "MrSwirlyEyes")
      )
      (libsource (lib "eagle-import") (part "1UF_CER_SMD-0402_25V-10%"))
    )
    (comp (ref "C134")
      (value "1uF/25V")
      (footprint "eagle-import:_CER_SMD_0402")
      (fields
        (field (name "MFR") "Murata Electronics North America")
        (field (name "MPN") "GRM155C81E105KE11D")
        (field (name "CREATOR") "MrSwirlyEyes")
      )
      (libsource (lib "eagle-import") (part "1UF_CER_SMD-0402_25V-10%"))
    )
    (comp (ref "C135")
      (value "0.1uF/50V")
      (footprint "eagle-import:_CER_SMD_0402")
      (fields
        (field (name "MFR") "Murata Electronics North America")
        (field (name "MPN") "GRM155R61H104KE19D")
        (field (name "CREATOR") "MrSwirlyEyes")
      )
      (libsource (lib "eagle-import") (part "0.1UF_SMD-0402_50V-10%"))
    )
    (comp (ref "C136")
      (value "1uF/25V")
      (footprint "eagle-import:_CER_SMD_0402")
      (fields
        (field (name "MFR") "Murata Electronics North America")
        (field (name "MPN") "GRM155C81E105KE11D")
        (field (name "CREATOR") "MrSwirlyEyes")
      )
      (libsource (lib "eagle-import") (part "1UF_CER_SMD-0402_25V-10%"))
    )
    (comp (ref "D1")
      (value "150mA/75V")
      (footprint "eagle-import:SOD-923F_0402")
      (fields
        (field (name "MFR") "Comchip Technology")
        (field (name "MPN") "CDSQR4148-HF")
        (field (name "CREATOR") "MrSwirlyEyes")
      )
      (libsource (lib "eagle-import") (part "DIODE_GENERAL-PURPOSE_SMD-0402_GP_120MA-75V"))
    )
    (comp (ref "D2")
      (value "150mA/75V")
      (footprint "eagle-import:SOD-923F_0402")
      (fields
        (field (name "MFR") "Comchip Technology")
        (field (name "MPN") "CDSQR4148-HF")
        (field (name "CREATOR") "MrSwirlyEyes")
      )
      (libsource (lib "eagle-import") (part "DIODE_GENERAL-PURPOSE_SMD-0402_GP_120MA-75V"))
    )
    (comp (ref "D3")
      (value "150mA/75V")
      (footprint "eagle-import:SOD-923F_0402")
      (fields
        (field (name "MFR") "Comchip Technology")
        (field (name "MPN") "CDSQR4148-HF")
        (field (name "CREATOR") "MrSwirlyEyes")
      )
      (libsource (lib "eagle-import") (part "DIODE_GENERAL-PURPOSE_SMD-0402_GP_120MA-75V"))
    )
    (comp (ref "D4")
      (value "150mA/75V")
      (footprint "eagle-import:SOD-923F_0402")
      (fields
        (field (name "MFR") "Comchip Technology")
        (field (name "MPN") "CDSQR4148-HF")
        (field (name "CREATOR") "MrSwirlyEyes")
      )
      (libsource (lib "eagle-import") (part "DIODE_GENERAL-PURPOSE_SMD-0402_GP_120MA-75V"))
    )
    (comp (ref "D5")
      (value "150mA/75V")
      (footprint "eagle-import:SOD-923F_0402")
      (fields
        (field (name "MFR") "Comchip Technology")
        (field (name "MPN") "CDSQR4148-HF")
        (field (name "CREATOR") "MrSwirlyEyes")
      )
      (libsource (lib "eagle-import") (part "DIODE_GENERAL-PURPOSE_SMD-0402_GP_120MA-75V"))
    )
    (comp (ref "D8")
      (value "1A/50V")
      (footprint "eagle-import:SOD123F")
      (fields
        (field (name "MFR") "Comchip Technology")
        (field (name "MPN") "CGRKM4001-HF")
        (field (name "CREATOR") "MrSwirlyEyes")
      )
      (libsource (lib "eagle-import") (part "DIODE_GENERAL-PURPOSE_SMD_GP_1A-50V"))
    )
    (comp (ref "D11")
      (value "150mA/75V")
      (footprint "eagle-import:SOD-923F_0402")
      (fields
        (field (name "MFR") "Comchip Technology")
        (field (name "MPN") "CDSQR4148-HF")
        (field (name "CREATOR") "MrSwirlyEyes")
      )
      (libsource (lib "eagle-import") (part "DIODE_GENERAL-PURPOSE_SMD-0402_GP_120MA-75V"))
    )
    (comp (ref "D12")
      (value "150mA/75V")
      (footprint "eagle-import:SOD-923F_0402")
      (fields
        (field (name "MFR") "Comchip Technology")
        (field (name "MPN") "CDSQR4148-HF")
        (field (name "CREATOR") "MrSwirlyEyes")
      )
      (libsource (lib "eagle-import") (part "DIODE_GENERAL-PURPOSE_SMD-0402_GP_120MA-75V"))
    )
    (comp (ref "D13")
      (value "1A/50V")
      (footprint "eagle-import:SOD123F")
      (fields
        (field (name "MFR") "Comchip Technology")
        (field (name "MPN") "CGRKM4001-HF")
        (field (name "CREATOR") "MrSwirlyEyes")
      )
      (libsource (lib "eagle-import") (part "DIODE_GENERAL-PURPOSE_SMD_GP_1A-50V"))
    )
    (comp (ref "D14")
      (value "1A/50V")
      (footprint "eagle-import:SOD123F")
      (fields
        (field (name "MFR") "Comchip Technology")
        (field (name "MPN") "CGRKM4001-HF")
        (field (name "CREATOR") "MrSwirlyEyes")
      )
      (libsource (lib "eagle-import") (part "DIODE_GENERAL-PURPOSE_SMD_GP_1A-50V"))
    )
    (comp (ref "DEMUX1")
      (value "CH16_MUX-DEMUX")
      (footprint "eagle-import:SSOP-24")
      (fields
        (field (name "MFR") "Texas Instruments")
        (field (name "MPN") "CD74HC4067SM96")
        (field (name "CREATOR") "MrSwirlyEyes")
      )
      (libsource (lib "eagle-import") (part "CD74HC4067-SM96_16{colon}1_MUX-DEMUX"))
    )
    (comp (ref "FLEX1")
      (value "10K")
      (footprint "eagle-import:CONNECTOR_FSR")
      (fields
        (field (name "MFR") "Spectra Symbol")
        (field (name "MPN") "FS-L-0055-103-ST?")
        (field (name "CREATOR") "MrSwirlyEyes")
      )
      (libsource (lib "eagle-import") (part "FLEX-SENSOR10K_2.2IN"))
    )
    (comp (ref "FLEX2")
      (value "10K")
      (footprint "eagle-import:CONNECTOR_FSR")
      (fields
        (field (name "MFR") "Spectra Symbol")
        (field (name "MPN") "FS-L-0055-103-ST?")
        (field (name "CREATOR") "MrSwirlyEyes")
      )
      (libsource (lib "eagle-import") (part "FLEX-SENSOR10K_2.2IN"))
    )
    (comp (ref "FLEX3")
      (value "10K")
      (footprint "eagle-import:CONNECTOR_FSR")
      (fields
        (field (name "MFR") "Spectra Symbol")
        (field (name "MPN") "FS-L-0055-103-ST?")
        (field (name "CREATOR") "MrSwirlyEyes")
      )
      (libsource (lib "eagle-import") (part "FLEX-SENSOR10K_2.2IN"))
    )
    (comp (ref "FLEX4")
      (value "10K")
      (footprint "eagle-import:CONNECTOR_FSR")
      (fields
        (field (name "MFR") "Spectra Symbol")
        (field (name "MPN") "FS-L-0055-103-ST?")
        (field (name "CREATOR") "MrSwirlyEyes")
      )
      (libsource (lib "eagle-import") (part "FLEX-SENSOR10K_2.2IN"))
    )
    (comp (ref "FLEX5")
      (value "10K")
      (footprint "eagle-import:CONNECTOR_FSR")
      (fields
        (field (name "MFR") "Spectra Symbol")
        (field (name "MPN") "FS-L-0055-103-ST?")
        (field (name "CREATOR") "MrSwirlyEyes")
      )
      (libsource (lib "eagle-import") (part "FLEX-SENSOR10K_2.2IN"))
    )
    (comp (ref "FLEX6")
      (value "10K")
      (footprint "eagle-import:CONNECTOR_FSR")
      (fields
        (field (name "MFR") "Spectra Symbol")
        (field (name "MPN") "FS-L-0055-103-ST?")
        (field (name "CREATOR") "MrSwirlyEyes")
      )
      (libsource (lib "eagle-import") (part "FLEX-SENSOR10K_2.2IN"))
    )
    (comp (ref "FLEX7")
      (value "10K")
      (footprint "eagle-import:CONNECTOR_FSR")
      (fields
        (field (name "MFR") "Spectra Symbol")
        (field (name "MPN") "FS-L-0055-103-ST?")
        (field (name "CREATOR") "MrSwirlyEyes")
      )
      (libsource (lib "eagle-import") (part "FLEX-SENSOR10K_2.2IN"))
    )
    (comp (ref "FLEX8")
      (value "10K")
      (footprint "eagle-import:CONNECTOR_FSR")
      (fields
        (field (name "MFR") "Spectra Symbol")
        (field (name "MPN") "FS-L-0055-103-ST?")
        (field (name "CREATOR") "MrSwirlyEyes")
      )
      (libsource (lib "eagle-import") (part "FLEX-SENSOR10K_2.2IN"))
    )
    (comp (ref "FLEX9")
      (value "10K")
      (footprint "eagle-import:CONNECTOR_FSR")
      (fields
        (field (name "MFR") "Spectra Symbol")
        (field (name "MPN") "FS-L-0055-103-ST?")
        (field (name "CREATOR") "MrSwirlyEyes")
      )
      (libsource (lib "eagle-import") (part "FLEX-SENSOR10K_2.2IN"))
    )
    (comp (ref "FLEX10")
      (value "10K")
      (footprint "eagle-import:CONNECTOR_FSR")
      (fields
        (field (name "MFR") "Spectra Symbol")
        (field (name "MPN") "FS-L-0055-103-ST?")
        (field (name "CREATOR") "MrSwirlyEyes")
      )
      (libsource (lib "eagle-import") (part "FLEX-SENSOR10K_2.2IN"))
    )
    (comp (ref "HBRIDGE1")
      (value "DRV8837C")
      (footprint "eagle-import:WSON-8-PPAD")
      (fields
        (field (name "MFR") "Texas Instruments")
        (field (name "MPN") "DRV8837CDSGT")
        (field (name "CREATOR") "MrSwirlyEyes")
      )
      (libsource (lib "eagle-import") (part "DRV883X_H-BRIDGE_DRV8837C_1A"))
    )
    (comp (ref "HBRIDGE2")
      (value "DRV8837C")
      (footprint "eagle-import:WSON-8-PPAD")
      (fields
        (field (name "MFR") "Texas Instruments")
        (field (name "MPN") "DRV8837CDSGT")
        (field (name "CREATOR") "MrSwirlyEyes")
      )
      (libsource (lib "eagle-import") (part "DRV883X_H-BRIDGE_DRV8837C_1A"))
    )
    (comp (ref "HBRIDGE3")
      (value "DRV8837C")
      (footprint "eagle-import:WSON-8-PPAD")
      (fields
        (field (name "MFR") "Texas Instruments")
        (field (name "MPN") "DRV8837CDSGT")
        (field (name "CREATOR") "MrSwirlyEyes")
      )
      (libsource (lib "eagle-import") (part "DRV883X_H-BRIDGE_DRV8837C_1A"))
    )
    (comp (ref "HBRIDGE4")
      (value "DRV8837C")
      (footprint "eagle-import:WSON-8-PPAD")
      (fields
        (field (name "MFR") "Texas Instruments")
        (field (name "MPN") "DRV8837CDSGT")
        (field (name "CREATOR") "MrSwirlyEyes")
      )
      (libsource (lib "eagle-import") (part "DRV883X_H-BRIDGE_DRV8837C_1A"))
    )
    (comp (ref "HBRIDGE5")
      (value "DRV8837C")
      (footprint "eagle-import:WSON-8-PPAD")
      (fields
        (field (name "MFR") "Texas Instruments")
        (field (name "MPN") "DRV8837CDSGT")
        (field (name "CREATOR") "MrSwirlyEyes")
      )
      (libsource (lib "eagle-import") (part "DRV883X_H-BRIDGE_DRV8837C_1A"))
    )
    (comp (ref "JP2")
      (value "FTDIPTH-RA")
      (footprint "eagle-import:FTDI_BASIC-6PIN-MALE-RA")
      (fields (field (name "MFR") "Amphenol FCI") (field (name "MPN") "68016-406HLF"))
      (libsource (lib "eagle-import") (part "FTDIPTH-RA"))
    )
    (comp (ref "L3")
      (value "10uH/0.38A")
      (footprint "eagle-import:_SMD-0603")
      (fields
        (field (name "MFR") "Taiyo Yuden")
        (field (name "MPN") "CBMF1608T100K")
        (field (name "CREATOR") "MrSwirlyEyes")
      )
      (libsource (lib "eagle-import") (part "10UH_SMD-0603_0.38A-0.468OHM-10%"))
    )
    (comp (ref "L4")
      (value "10uH/0.38A")
      (footprint "eagle-import:_SMD-0603")
      (fields
        (field (name "MFR") "Taiyo Yuden")
        (field (name "MPN") "CBMF1608T100K")
        (field (name "CREATOR") "MrSwirlyEyes")
      )
      (libsource (lib "eagle-import") (part "10UH_SMD-0603_0.38A-0.468OHM-10%"))
    )
    (comp (ref "LED1")
      (value "GREEN")
      (footprint "eagle-import:LED_SMD-0402")
      (fields
        (field (name "MFR") "Bivar Inc.")
        (field (name "MPN") "SM0402GC")
        (field (name "CREATOR") "MrSwirlyEyes")
      )
      (libsource (lib "eagle-import") (part "LED_SMD-0402_DISCRETE_GREEN"))
    )
    (comp (ref "LED2")
      (value "RED")
      (footprint "eagle-import:LED_SMD-0402")
      (fields
        (field (name "MFR") "Bivar Inc.")
        (field (name "MPN") "SM0402RC")
        (field (name "CREATOR") "MrSwirlyEyes")
      )
      (libsource (lib "eagle-import") (part "LED_SMD-0402_DISCRETE_RED"))
    )
    (comp (ref "LED3")
      (value "BLUE")
      (footprint "eagle-import:LED_SMD-0402")
      (fields
        (field (name "MFR") "Bivar Inc.")
        (field (name "MPN") "SM0402BWC")
        (field (name "CREATOR") "MrSwirlyEyes")
      )
      (libsource (lib "eagle-import") (part "LED_SMD-0402_DISCRETE_BLUE"))
    )
    (comp (ref "MCU")
      (value "ATMEGA128RFA1")
      (footprint "eagle-import:VFQFN-64")
      (fields
        (field (name "MFR") "Atmel")
        (field (name "MPN") "ATMEGA128RFA1-ZU ")
        (field (name "CREATOR") "Kenmei")
      )
      (libsource (lib "eagle-import") (part "ATMEGA128RFA1_VFQFN-64_EXPOSED-PAD"))
    )
    (comp (ref "NOISE_BR")
      (value "2PT_GND_TIE")
      (footprint "eagle-import:2PT_GND_TIE")
      (libsource (lib "eagle-import") (part "2PT_GND_TIE"))
    )
    (comp (ref "PWM_DRIVER1")
      (value "PCA9685")
      (footprint "eagle-import:TSSOP-28")
      (fields
        (field (name "MFR") "NXP USA Inc.")
        (field (name "MPN") "PCA9685PW,118")
        (field (name "CREATOR") "MrSwirlyEyes")
      )
      (libsource (lib "eagle-import") (part "PCA9685_16-CH_12-BIT_PWM-DRIVER"))
    )
    (comp (ref "Q1")
      (value "MCH3474 4A/30V/50mΩ")
      (footprint "eagle-import:SC-70FL_MCPH3")
      (fields
        (field (name "MFR") "ON Semiconductor")
        (field (name "MPN") "MCH3474-TL-W")
        (field (name "CREATOR") "Kenmei")
      )
      (libsource (lib "eagle-import") (part "POWER_NCHAN_MCH3474"))
    )
    (comp (ref "Q2")
      (value "MCH3474 4A/30V/50mΩ")
      (footprint "eagle-import:SC-70FL_MCPH3")
      (fields
        (field (name "MFR") "ON Semiconductor")
        (field (name "MPN") "MCH3474-TL-W")
        (field (name "CREATOR") "Kenmei")
      )
      (libsource (lib "eagle-import") (part "POWER_NCHAN_MCH3474"))
    )
    (comp (ref "Q3")
      (value "MCH3474 4A/30V/50mΩ")
      (footprint "eagle-import:SC-70FL_MCPH3")
      (fields
        (field (name "MFR") "ON Semiconductor")
        (field (name "MPN") "MCH3474-TL-W")
        (field (name "CREATOR") "Kenmei")
      )
      (libsource (lib "eagle-import") (part "POWER_NCHAN_MCH3474"))
    )
    (comp (ref "Q4")
      (value "MCH3474 4A/30V/50mΩ")
      (footprint "eagle-import:SC-70FL_MCPH3")
      (fields
        (field (name "MFR") "ON Semiconductor")
        (field (name "MPN") "MCH3474-TL-W")
        (field (name "CREATOR") "Kenmei")
      )
      (libsource (lib "eagle-import") (part "POWER_NCHAN_MCH3474"))
    )
    (comp (ref "Q5")
      (value "MCH3474 4A/30V/50mΩ")
      (footprint "eagle-import:SC-70FL_MCPH3")
      (fields
        (field (name "MFR") "ON Semiconductor")
        (field (name "MPN") "MCH3474-TL-W")
        (field (name "CREATOR") "Kenmei")
      )
      (libsource (lib "eagle-import") (part "POWER_NCHAN_MCH3474"))
    )
    (comp (ref "Q6")
      (value "MCH3474 4A/30V/50mΩ")
      (footprint "eagle-import:SC-70FL_MCPH3")
      (fields
        (field (name "MFR") "ON Semiconductor")
        (field (name "MPN") "MCH3474-TL-W")
        (field (name "CREATOR") "Kenmei")
      )
      (libsource (lib "eagle-import") (part "POWER_NCHAN_MCH3474"))
    )
    (comp (ref "R1")
      (value "10KΩ")
      (footprint "eagle-import:RESISTOR_SMD-0402")
      (fields
        (field (name "MFR") "Yageo")
        (field (name "MPN") "RC0402JR-0710KL")
        (field (name "CREATOR") "MrSwirlyEyes")
      )
      (libsource (lib "eagle-import") (part "10KΩ_SMD-0402_1/16W-5%"))
    )
    (comp (ref "R2")
      (value "10KΩ")
      (footprint "eagle-import:RESISTOR_SMD-0402")
      (fields
        (field (name "MFR") "Yageo")
        (field (name "MPN") "RC0402JR-0710KL")
        (field (name "CREATOR") "MrSwirlyEyes")
      )
      (libsource (lib "eagle-import") (part "10KΩ_SMD-0402_1/16W-5%"))
    )
    (comp (ref "R3")
      (value "10KΩ")
      (footprint "eagle-import:RESISTOR_SMD-0402")
      (fields
        (field (name "MFR") "Yageo")
        (field (name "MPN") "RC0402JR-0710KL")
        (field (name "CREATOR") "MrSwirlyEyes")
      )
      (libsource (lib "eagle-import") (part "10KΩ_SMD-0402_1/16W-5%"))
    )
    (comp (ref "R4")
      (value "10KΩ")
      (footprint "eagle-import:RESISTOR_SMD-0402")
      (fields
        (field (name "MFR") "Yageo")
        (field (name "MPN") "RC0402JR-0710KL")
        (field (name "CREATOR") "MrSwirlyEyes")
      )
      (libsource (lib "eagle-import") (part "10KΩ_SMD-0402_1/16W-5%"))
    )
    (comp (ref "R5")
      (value "10KΩ")
      (footprint "eagle-import:RESISTOR_SMD-0402")
      (fields
        (field (name "MFR") "Yageo")
        (field (name "MPN") "RC0402JR-0710KL")
        (field (name "CREATOR") "MrSwirlyEyes")
      )
      (libsource (lib "eagle-import") (part "10KΩ_SMD-0402_1/16W-5%"))
    )
    (comp (ref "R6")
      (value "100Ω")
      (footprint "eagle-import:RESISTOR_SMD-0402")
      (fields
        (field (name "MFR") "Yageo")
        (field (name "MPN") "RC0402JR-07100RL")
        (field (name "CREATOR") "MrSwirlyEyes")
      )
      (libsource (lib "eagle-import") (part "100Ω_SMD-0402_1/16W-5%"))
    )
    (comp (ref "R7")
      (value "100Ω")
      (footprint "eagle-import:RESISTOR_SMD-0402")
      (fields
        (field (name "MFR") "Yageo")
        (field (name "MPN") "RC0402JR-07100RL")
        (field (name "CREATOR") "MrSwirlyEyes")
      )
      (libsource (lib "eagle-import") (part "100Ω_SMD-0402_1/16W-5%"))
    )
    (comp (ref "R8")
      (value "100Ω")
      (footprint "eagle-import:RESISTOR_SMD-0402")
      (fields
        (field (name "MFR") "Yageo")
        (field (name "MPN") "RC0402JR-07100RL")
        (field (name "CREATOR") "MrSwirlyEyes")
      )
      (libsource (lib "eagle-import") (part "100Ω_SMD-0402_1/16W-5%"))
    )
    (comp (ref "R9")
      (value "100Ω")
      (footprint "eagle-import:RESISTOR_SMD-0402")
      (fields
        (field (name "MFR") "Yageo")
        (field (name "MPN") "RC0402JR-07100RL")
        (field (name "CREATOR") "MrSwirlyEyes")
      )
      (libsource (lib "eagle-import") (part "100Ω_SMD-0402_1/16W-5%"))
    )
    (comp (ref "R10")
      (value "100Ω")
      (footprint "eagle-import:RESISTOR_SMD-0402")
      (fields
        (field (name "MFR") "Yageo")
        (field (name "MPN") "RC0402JR-07100RL")
        (field (name "CREATOR") "MrSwirlyEyes")
      )
      (libsource (lib "eagle-import") (part "100Ω_SMD-0402_1/16W-5%"))
    )
    (comp (ref "R11")
      (value "47KΩ")
      (footprint "eagle-import:RESISTOR_SMD-0402")
      (fields
        (field (name "MFR") "Yageo")
        (field (name "MPN") "RC0402JR-0747KL")
        (field (name "CREATOR") "MrSwirlyEyes")
      )
      (libsource (lib "eagle-import") (part "47KΩ_SMD-0402_1/16W-5%"))
    )
    (comp (ref "R12")
      (value "10KΩ")
      (footprint "eagle-import:RESISTOR_SMD-0402")
      (fields
        (field (name "MFR") "Yageo")
        (field (name "MPN") "RC0402JR-0710KL")
        (field (name "CREATOR") "MrSwirlyEyes")
      )
      (libsource (lib "eagle-import") (part "10KΩ_SMD-0402_1/16W-5%"))
    )
    (comp (ref "R13")
      (value "100Ω")
      (footprint "eagle-import:RESISTOR_SMD-0402")
      (fields
        (field (name "MFR") "Yageo")
        (field (name "MPN") "RC0402JR-07100RL")
        (field (name "CREATOR") "MrSwirlyEyes")
      )
      (libsource (lib "eagle-import") (part "100Ω_SMD-0402_1/16W-5%"))
    )
    (comp (ref "R14")
      (value "10KΩ")
      (footprint "eagle-import:RESISTOR_SMD-0402")
      (fields
        (field (name "MFR") "Yageo")
        (field (name "MPN") "RC0402JR-0710KL")
        (field (name "CREATOR") "MrSwirlyEyes")
      )
      (libsource (lib "eagle-import") (part "10KΩ_SMD-0402_1/16W-5%"))
    )
    (comp (ref "R15")
      (value "100Ω")
      (footprint "eagle-import:RESISTOR_SMD-0402")
      (fields
        (field (name "MFR") "Yageo")
        (field (name "MPN") "RC0402JR-07100RL")
        (field (name "CREATOR") "MrSwirlyEyes")
      )
      (libsource (lib "eagle-import") (part "100Ω_SMD-0402_1/16W-5%"))
    )
    (comp (ref "R16")
      (value "10KΩ")
      (footprint "eagle-import:RESISTOR_SMD-0402")
      (fields
        (field (name "MFR") "Yageo")
        (field (name "MPN") "RC0402JR-0710KL")
        (field (name "CREATOR") "MrSwirlyEyes")
      )
      (libsource (lib "eagle-import") (part "10KΩ_SMD-0402_1/16W-5%"))
    )
    (comp (ref "R17")
      (value "100Ω")
      (footprint "eagle-import:RESISTOR_SMD-0402")
      (fields
        (field (name "MFR") "Yageo")
        (field (name "MPN") "RC0402JR-07100RL")
        (field (name "CREATOR") "MrSwirlyEyes")
      )
      (libsource (lib "eagle-import") (part "100Ω_SMD-0402_1/16W-5%"))
    )
    (comp (ref "R18")
      (value "10KΩ")
      (footprint "eagle-import:RESISTOR_SMD-0402")
      (fields
        (field (name "MFR") "Yageo")
        (field (name "MPN") "RC0402JR-0710KL")
        (field (name "CREATOR") "MrSwirlyEyes")
      )
      (libsource (lib "eagle-import") (part "10KΩ_SMD-0402_1/16W-5%"))
    )
    (comp (ref "R19")
      (value "100Ω")
      (footprint "eagle-import:RESISTOR_SMD-0402")
      (fields
        (field (name "MFR") "Yageo")
        (field (name "MPN") "RC0402JR-07100RL")
        (field (name "CREATOR") "MrSwirlyEyes")
      )
      (libsource (lib "eagle-import") (part "100Ω_SMD-0402_1/16W-5%"))
    )
    (comp (ref "R20")
      (value "10KΩ")
      (footprint "eagle-import:RESISTOR_SMD-0402")
      (fields
        (field (name "MFR") "Yageo")
        (field (name "MPN") "RC0402JR-0710KL")
        (field (name "CREATOR") "MrSwirlyEyes")
      )
      (libsource (lib "eagle-import") (part "10KΩ_SMD-0402_1/16W-5%"))
    )
    (comp (ref "R21")
      (value "100Ω")
      (footprint "eagle-import:RESISTOR_SMD-0402")
      (fields
        (field (name "MFR") "Yageo")
        (field (name "MPN") "RC0402JR-07100RL")
        (field (name "CREATOR") "MrSwirlyEyes")
      )
      (libsource (lib "eagle-import") (part "100Ω_SMD-0402_1/16W-5%"))
    )
    (comp (ref "R22")
      (value "10KΩ")
      (footprint "eagle-import:RESISTOR_SMD-0402")
      (fields
        (field (name "MFR") "Yageo")
        (field (name "MPN") "RC0402JR-0710KL")
        (field (name "CREATOR") "MrSwirlyEyes")
      )
      (libsource (lib "eagle-import") (part "10KΩ_SMD-0402_1/16W-5%"))
    )
    (comp (ref "R23")
      (value "100Ω")
      (footprint "eagle-import:RESISTOR_SMD-0402")
      (fields
        (field (name "MFR") "Yageo")
        (field (name "MPN") "RC0402JR-07100RL")
        (field (name "CREATOR") "MrSwirlyEyes")
      )
      (libsource (lib "eagle-import") (part "100Ω_SMD-0402_1/16W-5%"))
    )
    (comp (ref "R24")
      (value "10KΩ")
      (footprint "eagle-import:RESISTOR_SMD-0402")
      (fields
        (field (name "MFR") "Yageo")
        (field (name "MPN") "RC0402JR-0710KL")
        (field (name "CREATOR") "MrSwirlyEyes")
      )
      (libsource (lib "eagle-import") (part "10KΩ_SMD-0402_1/16W-5%"))
    )
    (comp (ref "R25")
      (value "100Ω")
      (footprint "eagle-import:RESISTOR_SMD-0402")
      (fields
        (field (name "MFR") "Yageo")
        (field (name "MPN") "RC0402JR-07100RL")
        (field (name "CREATOR") "MrSwirlyEyes")
      )
      (libsource (lib "eagle-import") (part "100Ω_SMD-0402_1/16W-5%"))
    )
    (comp (ref "R26")
      (value "10KΩ")
      (footprint "eagle-import:RESISTOR_SMD-0402")
      (fields
        (field (name "MFR") "Yageo")
        (field (name "MPN") "RC0402JR-0710KL")
        (field (name "CREATOR") "MrSwirlyEyes")
      )
      (libsource (lib "eagle-import") (part "10KΩ_SMD-0402_1/16W-5%"))
    )
    (comp (ref "R27")
      (value "100Ω")
      (footprint "eagle-import:RESISTOR_SMD-0402")
      (fields
        (field (name "MFR") "Yageo")
        (field (name "MPN") "RC0402JR-07100RL")
        (field (name "CREATOR") "MrSwirlyEyes")
      )
      (libsource (lib "eagle-import") (part "100Ω_SMD-0402_1/16W-5%"))
    )
    (comp (ref "R28")
      (value "10KΩ")
      (footprint "eagle-import:RESISTOR_SMD-0402")
      (fields
        (field (name "MFR") "Yageo")
        (field (name "MPN") "RC0402JR-0710KL")
        (field (name "CREATOR") "MrSwirlyEyes")
      )
      (libsource (lib "eagle-import") (part "10KΩ_SMD-0402_1/16W-5%"))
    )
    (comp (ref "R29")
      (value "100Ω")
      (footprint "eagle-import:RESISTOR_SMD-0402")
      (fields
        (field (name "MFR") "Yageo")
        (field (name "MPN") "RC0402JR-07100RL")
        (field (name "CREATOR") "MrSwirlyEyes")
      )
      (libsource (lib "eagle-import") (part "100Ω_SMD-0402_1/16W-5%"))
    )
    (comp (ref "R30")
      (value "10KΩ")
      (footprint "eagle-import:RESISTOR_SMD-0402")
      (fields
        (field (name "MFR") "Yageo")
        (field (name "MPN") "RC0402JR-0710KL")
        (field (name "CREATOR") "MrSwirlyEyes")
      )
      (libsource (lib "eagle-import") (part "10KΩ_SMD-0402_1/16W-5%"))
    )
    (comp (ref "R31")
      (value "100Ω")
      (footprint "eagle-import:RESISTOR_SMD-0402")
      (fields
        (field (name "MFR") "Yageo")
        (field (name "MPN") "RC0402JR-07100RL")
        (field (name "CREATOR") "MrSwirlyEyes")
      )
      (libsource (lib "eagle-import") (part "100Ω_SMD-0402_1/16W-5%"))
    )
    (comp (ref "R32")
      (value "10KΩ")
      (footprint "eagle-import:RESISTOR_SMD-0402")
      (fields
        (field (name "MFR") "Yageo")
        (field (name "MPN") "RC0402JR-0710KL")
        (field (name "CREATOR") "MrSwirlyEyes")
      )
      (libsource (lib "eagle-import") (part "10KΩ_SMD-0402_1/16W-5%"))
    )
    (comp (ref "R33")
      (value "100Ω")
      (footprint "eagle-import:RESISTOR_SMD-0402")
      (fields
        (field (name "MFR") "Yageo")
        (field (name "MPN") "RC0402JR-07100RL")
        (field (name "CREATOR") "MrSwirlyEyes")
      )
      (libsource (lib "eagle-import") (part "100Ω_SMD-0402_1/16W-5%"))
    )
    (comp (ref "R34")
      (value "47KΩ")
      (footprint "eagle-import:RESISTOR_SMD-0402")
      (fields
        (field (name "MFR") "Yageo")
        (field (name "MPN") "RC0402JR-0747KL")
        (field (name "CREATOR") "MrSwirlyEyes")
      )
      (libsource (lib "eagle-import") (part "47KΩ_SMD-0402_1/16W-5%"))
    )
    (comp (ref "R35")
      (value "47KΩ")
      (footprint "eagle-import:RESISTOR_SMD-0402")
      (fields
        (field (name "MFR") "Yageo")
        (field (name "MPN") "RC0402JR-0747KL")
        (field (name "CREATOR") "MrSwirlyEyes")
      )
      (libsource (lib "eagle-import") (part "47KΩ_SMD-0402_1/16W-5%"))
    )
    (comp (ref "R36")
      (value "47KΩ")
      (footprint "eagle-import:RESISTOR_SMD-0402")
      (fields
        (field (name "MFR") "Yageo")
        (field (name "MPN") "RC0402JR-0747KL")
        (field (name "CREATOR") "MrSwirlyEyes")
      )
      (libsource (lib "eagle-import") (part "47KΩ_SMD-0402_1/16W-5%"))
    )
    (comp (ref "R37")
      (value "47KΩ")
      (footprint "eagle-import:RESISTOR_SMD-0402")
      (fields
        (field (name "MFR") "Yageo")
        (field (name "MPN") "RC0402JR-0747KL")
        (field (name "CREATOR") "MrSwirlyEyes")
      )
      (libsource (lib "eagle-import") (part "47KΩ_SMD-0402_1/16W-5%"))
    )
    (comp (ref "R38")
      (value "47KΩ")
      (footprint "eagle-import:RESISTOR_SMD-0402")
      (fields
        (field (name "MFR") "Yageo")
        (field (name "MPN") "RC0402JR-0747KL")
        (field (name "CREATOR") "MrSwirlyEyes")
      )
      (libsource (lib "eagle-import") (part "47KΩ_SMD-0402_1/16W-5%"))
    )
    (comp (ref "R39")
      (value "47KΩ")
      (footprint "eagle-import:RESISTOR_SMD-0402")
      (fields
        (field (name "MFR") "Yageo")
        (field (name "MPN") "RC0402JR-0747KL")
        (field (name "CREATOR") "MrSwirlyEyes")
      )
      (libsource (lib "eagle-import") (part "47KΩ_SMD-0402_1/16W-5%"))
    )
    (comp (ref "R40")
      (value "4.7KΩ")
      (footprint "eagle-import:RESISTOR_SMD-0402")
      (fields
        (field (name "MFR") "Yageo")
        (field (name "MPN") "RC0402JR-074K7L")
        (field (name "CREATOR") "MrSwirlyEyes")
      )
      (libsource (lib "eagle-import") (part "4.7KΩ_SMD-0402_1/16W-5%"))
    )
    (comp (ref "R41")
      (value "4.7KΩ")
      (footprint "eagle-import:RESISTOR_SMD-0402")
      (fields
        (field (name "MFR") "Yageo")
        (field (name "MPN") "RC0402JR-074K7L")
        (field (name "CREATOR") "MrSwirlyEyes")
      )
      (libsource (lib "eagle-import") (part "4.7KΩ_SMD-0402_1/16W-5%"))
    )
    (comp (ref "R42")
      (value "47KΩ")
      (footprint "eagle-import:RESISTOR_SMD-0402")
      (fields
        (field (name "MFR") "Yageo")
        (field (name "MPN") "RC0402JR-0747KL")
        (field (name "CREATOR") "MrSwirlyEyes")
      )
      (libsource (lib "eagle-import") (part "47KΩ_SMD-0402_1/16W-5%"))
    )
    (comp (ref "R43")
      (value "47KΩ")
      (footprint "eagle-import:RESISTOR_SMD-0402")
      (fields
        (field (name "MFR") "Yageo")
        (field (name "MPN") "RC0402JR-0747KL")
        (field (name "CREATOR") "MrSwirlyEyes")
      )
      (libsource (lib "eagle-import") (part "47KΩ_SMD-0402_1/16W-5%"))
    )
    (comp (ref "R44")
      (value "47KΩ")
      (footprint "eagle-import:RESISTOR_SMD-0402")
      (fields
        (field (name "MFR") "Yageo")
        (field (name "MPN") "RC0402JR-0747KL")
        (field (name "CREATOR") "MrSwirlyEyes")
      )
      (libsource (lib "eagle-import") (part "47KΩ_SMD-0402_1/16W-5%"))
    )
    (comp (ref "R46")
      (value "10KΩ")
      (footprint "eagle-import:RESISTOR_SMD-0402")
      (fields
        (field (name "MFR") "Yageo")
        (field (name "MPN") "RC0402JR-0710KL")
        (field (name "CREATOR") "MrSwirlyEyes")
      )
      (libsource (lib "eagle-import") (part "10KΩ_SMD-0402_1/16W-5%"))
    )
    (comp (ref "R47")
      (value "10KΩ")
      (footprint "eagle-import:RESISTOR_SMD-0402")
      (fields
        (field (name "MFR") "Yageo")
        (field (name "MPN") "RC0402JR-0710KL")
        (field (name "CREATOR") "MrSwirlyEyes")
      )
      (libsource (lib "eagle-import") (part "10KΩ_SMD-0402_1/16W-5%"))
    )
    (comp (ref "R48")
      (value "2KΩ")
      (footprint "eagle-import:RESISTOR_SMD-0402")
      (fields
        (field (name "MFR") "Yageo")
        (field (name "MPN") "RC0402JR-072KL")
        (field (name "CREATOR") "MrSwirlyEyes")
      )
      (libsource (lib "eagle-import") (part "2KΩ_SMD-0402_1/16W-5%"))
    )
    (comp (ref "R49")
      (value "1KΩ")
      (footprint "eagle-import:RESISTOR_SMD-0402")
      (fields
        (field (name "MFR") "Yageo")
        (field (name "MPN") "RC0402JR-071KL")
        (field (name "CREATOR") "MrSwirlyEyes")
      )
      (libsource (lib "eagle-import") (part "1KΩ_SMD-0402_1/16W-5%"))
    )
    (comp (ref "SW1")
      (value "4A/28V")
      (footprint "eagle-import:SW_SLIDE_RA_SPDT_4A-28V_L12.7-W9.5")
      (fields
        (field (name "MFR") "E-Switch")
        (field (name "MPN") "500SSP1S1M6QEA")
        (field (name "CREATOR") "MrSwirlyEyes")
      )
      (libsource (lib "eagle-import") (part "SWITCH_SPDT_RA_PTH_4A-28V_L12.7-W9.5"))
    )
    (comp (ref "TEC1")
      (value "PELTIER")
      (footprint "eagle-import:CONNECTOR_PELTIER")
      (fields
        (field (name "MFR") "Marlow Industries, Inc.")
        (field (name "MPN") "NL1025T-01AC")
        (field (name "CREATOR") "MrSwirlyEyes")
      )
      (libsource (lib "eagle-import") (part "PELTIER-TECNL1025T_1.8A-4.4V_L10.7-W8.8-H2"))
    )
    (comp (ref "TEC2")
      (value "PELTIER")
      (footprint "eagle-import:CONNECTOR_PELTIER")
      (fields
        (field (name "MFR") "Marlow Industries, Inc.")
        (field (name "MPN") "NL1025T-01AC")
        (field (name "CREATOR") "MrSwirlyEyes")
      )
      (libsource (lib "eagle-import") (part "PELTIER-TECNL1025T_1.8A-4.4V_L10.7-W8.8-H2"))
    )
    (comp (ref "TEC3")
      (value "PELTIER")
      (footprint "eagle-import:CONNECTOR_PELTIER")
      (fields
        (field (name "MFR") "Marlow Industries, Inc.")
        (field (name "MPN") "NL1025T-01AC")
        (field (name "CREATOR") "MrSwirlyEyes")
      )
      (libsource (lib "eagle-import") (part "PELTIER-TECNL1025T_1.8A-4.4V_L10.7-W8.8-H2"))
    )
    (comp (ref "TEC4")
      (value "PELTIER")
      (footprint "eagle-import:CONNECTOR_PELTIER")
      (fields
        (field (name "MFR") "Marlow Industries, Inc.")
        (field (name "MPN") "NL1025T-01AC")
        (field (name "CREATOR") "MrSwirlyEyes")
      )
      (libsource (lib "eagle-import") (part "PELTIER-TECNL1025T_1.8A-4.4V_L10.7-W8.8-H2"))
    )
    (comp (ref "TEC5")
      (value "PELTIER")
      (footprint "eagle-import:CONNECTOR_PELTIER")
      (fields
        (field (name "MFR") "Marlow Industries, Inc.")
        (field (name "MPN") "NL1025T-01AC")
        (field (name "CREATOR") "MrSwirlyEyes")
      )
      (libsource (lib "eagle-import") (part "PELTIER-TECNL1025T_1.8A-4.4V_L10.7-W8.8-H2"))
    )
    (comp (ref "VIBE1")
      (value "VIBE_MOTOR")
      (footprint "eagle-import:CONNECTOR_VIBE-MOTOR")
      (fields
        (field (name "MFR") "Jinlong Machinery & Electronics, Inc.")
        (field (name "MPN") "C0825B002F")
        (field (name "CREATOR") "MrSwirlyEyes")
      )
      (libsource (lib "eagle-import") (part "VIBE_MOTOR_100MA/3V"))
    )
    (comp (ref "VIBE2")
      (value "VIBE_MOTOR")
      (footprint "eagle-import:CONNECTOR_VIBE-MOTOR")
      (fields
        (field (name "MFR") "Jinlong Machinery & Electronics, Inc.")
        (field (name "MPN") "C0825B002F")
        (field (name "CREATOR") "MrSwirlyEyes")
      )
      (libsource (lib "eagle-import") (part "VIBE_MOTOR_100MA/3V"))
    )
    (comp (ref "VIBE3")
      (value "VIBE_MOTOR")
      (footprint "eagle-import:CONNECTOR_VIBE-MOTOR")
      (fields
        (field (name "MFR") "Jinlong Machinery & Electronics, Inc.")
        (field (name "MPN") "C0825B002F")
        (field (name "CREATOR") "MrSwirlyEyes")
      )
      (libsource (lib "eagle-import") (part "VIBE_MOTOR_100MA/3V"))
    )
    (comp (ref "VIBE4")
      (value "VIBE_MOTOR")
      (footprint "eagle-import:CONNECTOR_VIBE-MOTOR")
      (fields
        (field (name "MFR") "Jinlong Machinery & Electronics, Inc.")
        (field (name "MPN") "C0825B002F")
        (field (name "CREATOR") "MrSwirlyEyes")
      )
      (libsource (lib "eagle-import") (part "VIBE_MOTOR_100MA/3V"))
    )
    (comp (ref "VIBE5")
      (value "VIBE_MOTOR")
      (footprint "eagle-import:CONNECTOR_VIBE-MOTOR")
      (fields
        (field (name "MFR") "Jinlong Machinery & Electronics, Inc.")
        (field (name "MPN") "C0825B002F")
        (field (name "CREATOR") "MrSwirlyEyes")
      )
      (libsource (lib "eagle-import") (part "VIBE_MOTOR_100MA/3V"))
    )
    (comp (ref "VIBE6")
      (value "VIBE_MOTOR")
      (footprint "eagle-import:CONNECTOR_VIBE-MOTOR")
      (fields
        (field (name "MFR") "Jinlong Machinery & Electronics, Inc.")
        (field (name "MPN") "C0825B002F")
        (field (name "CREATOR") "MrSwirlyEyes")
      )
      (libsource (lib "eagle-import") (part "VIBE_MOTOR_100MA/3V"))
    )
    (comp (ref "VREG1")
      (value "1A/3.3V")
      (footprint "eagle-import:SOIC-8_W3.9MM")
      (fields
        (field (name "MFR") "Texas Instruments")
        (field (name "MPN") "TPS76833QDR")
        (field (name "CREATOR") "MrSwirlyEyes")
      )
      (libsource (lib "eagle-import") (part "VREG_TPS76833_ULDO_FAST-TRANSIENT_1A-3.3VTPS76833QDR_1A-3.3V"))
    )
    (comp (ref "VREG6")
      (value "TL1963A-33 1.5A/3.3V")
      (footprint "eagle-import:SOT223-4")
      (fields
        (field (name "MFR") "Texas Instruments")
        (field (name "MPN") "TL1963A-33DCYR")
        (field (name "CREATOR") "MrSwirlyEyes")
      )
      (libsource (lib "eagle-import") (part "VREG_LINEAR_FIXED_TL1963A-33_LDO_1.5A-3.3V"))
    )
    (comp (ref "VREG7")
      (value "3A/1.8V")
      (footprint "eagle-import:DDPAK-5")
      (fields
        (field (name "MFR") "Linear Technology")
        (field (name "MPN") "LT1764EQ-1.8#PBF")
        (field (name "CREATOR") "MrSwirlyEyes")
      )
      (libsource (lib "eagle-import") (part "VREG_LT1764EQ_ULDO_FAST-TRANSIENT_LT1764EQ-1.8_3A-1.8V"))
    )
    (comp (ref "Y2")
      (value "16MHz")
      (footprint "eagle-import:CRYSTAL-SMD-5X3")
      (fields (field (name "MFR") "Abracon LLC") (field (name "MPN") "ABM3B-16.000MHZ-B2-T"))
      (libsource (lib "eagle-import") (part "CRYSTAL_ABM3B_16MHZ_18PF"))
    )
  )
  (nets
    (net (code "1") (name "1.8V") (class "Default")
      (node (ref "C10") (pin "1") (pinfunction "1_1") (pintype "passive"))
      (node (ref "C13") (pin "1") (pinfunction "1_1") (pintype "passive"))
      (node (ref "C14") (pin "1") (pinfunction "1_1") (pintype "passive"))
      (node (ref "C17") (pin "1") (pinfunction "1_1") (pintype "passive"))
      (node (ref "C18") (pin "1") (pinfunction "1_1") (pintype "passive"))
      (node (ref "C21") (pin "1") (pinfunction "1_1") (pintype "passive"))
      (node (ref "C22") (pin "1") (pinfunction "1_1") (pintype "passive"))
      (node (ref "C26") (pin "1") (pinfunction "1_1") (pintype "passive"))
      (node (ref "C27") (pin "1") (pinfunction "1_1") (pintype "passive"))
      (node (ref "C39") (pin "1") (pinfunction "1_1") (pintype "passive"))
      (node (ref "C40") (pin "1") (pinfunction "1_1") (pintype "passive"))
      (node (ref "C42") (pin "1") (pinfunction "1_1") (pintype "passive"))
      (node (ref "C9") (pin "1") (pinfunction "1_1") (pintype "passive"))
      (node (ref "D14") (pin "A") (pinfunction "A_A") (pintype "passive"))
      (node (ref "HBRIDGE1") (pin "1") (pinfunction "VM_1") (pintype "passive"))
      (node (ref "HBRIDGE2") (pin "1") (pinfunction "VM_1") (pintype "passive"))
      (node (ref "HBRIDGE3") (pin "1") (pinfunction "VM_1") (pintype "passive"))
      (node (ref "HBRIDGE4") (pin "1") (pinfunction "VM_1") (pintype "passive"))
      (node (ref "HBRIDGE5") (pin "1") (pinfunction "VM_1") (pintype "passive"))
      (node (ref "VREG7") (pin "4") (pinfunction "VOUT_4") (pintype "bidirectional"))
      (node (ref "VREG7") (pin "5") (pinfunction "SENSE_5") (pintype "bidirectional"))
    )
    (net (code "2") (name "3.3V") (class "Default")
      (node (ref "C1") (pin "1") (pinfunction "1_1") (pintype "passive"))
      (node (ref "C3") (pin "1") (pinfunction "1_1") (pintype "passive"))
      (node (ref "C36") (pin "1") (pinfunction "1_1") (pintype "passive"))
      (node (ref "C4") (pin "1") (pinfunction "1_1") (pintype "passive"))
      (node (ref "C41") (pin "1") (pinfunction "1_1") (pintype "passive"))
      (node (ref "C43") (pin "1") (pinfunction "1_1") (pintype "passive"))
      (node (ref "C5") (pin "1") (pinfunction "1_1") (pintype "passive"))
      (node (ref "C6") (pin "1") (pinfunction "1_1") (pintype "passive"))
      (node (ref "C7") (pin "1") (pinfunction "1_1") (pintype "passive"))
      (node (ref "D1") (pin "K") (pinfunction "K_K") (pintype "passive"))
      (node (ref "D12") (pin "K") (pinfunction "K_K") (pintype "passive"))
      (node (ref "D13") (pin "A") (pinfunction "A_A") (pintype "passive"))
      (node (ref "D2") (pin "K") (pinfunction "K_K") (pintype "passive"))
      (node (ref "D3") (pin "K") (pinfunction "K_K") (pintype "passive"))
      (node (ref "D4") (pin "K") (pinfunction "K_K") (pintype "passive"))
      (node (ref "D5") (pin "K") (pinfunction "K_K") (pintype "passive"))
      (node (ref "VIBE1") (pin "1") (pinfunction "+_1") (pintype "passive"))
      (node (ref "VIBE2") (pin "1") (pinfunction "+_1") (pintype "passive"))
      (node (ref "VIBE3") (pin "1") (pinfunction "+_1") (pintype "passive"))
      (node (ref "VIBE4") (pin "1") (pinfunction "+_1") (pintype "passive"))
      (node (ref "VIBE5") (pin "1") (pinfunction "+_1") (pintype "passive"))
      (node (ref "VIBE6") (pin "1") (pinfunction "+_1") (pintype "passive"))
      (node (ref "VREG6") (pin "3") (pinfunction "VO_3") (pintype "bidirectional"))
    )
    (net (code "3") (name "A0") (class "Default")
      (node (ref "MCU") (pin "63") (pinfunction "(ADC0/A0*)PF0_63") (pintype "bidirectional"))
    )
    (net (code "4") (name "A1") (class "Default")
      (node (ref "DEMUX1") (pin "1") (pinfunction "SIG_1") (pintype "passive"))
      (node (ref "MCU") (pin "64") (pinfunction "(ADC1/A1*)PF1_64") (pintype "bidirectional"))
    )
    (net (code "5") (name "A2") (class "Default")
      (node (ref "MCU") (pin "1") (pinfunction "(ADC2/DIG2/A2*)PF2_1") (pintype "bidirectional"))
    )
    (net (code "6") (name "A3") (class "Default")
      (node (ref "MCU") (pin "2") (pinfunction "(ADC3/DIG4/A3*)PF3_2") (pintype "bidirectional"))
    )
    (net (code "7") (name "A4") (class "Default")
      (node (ref "MCU") (pin "3") (pinfunction "(ADC4/TCK/A4*)PF4_3") (pintype "bidirectional"))
    )
    (net (code "8") (name "A5") (class "Default")
      (node (ref "MCU") (pin "4") (pinfunction "(ADC5/TMS/A5*)PF5_4") (pintype "bidirectional"))
    )
    (net (code "9") (name "A6") (class "Default")
      (node (ref "MCU") (pin "5") (pinfunction "(ADC6/TDO/A6*)PF6_5") (pintype "bidirectional"))
    )
    (net (code "10") (name "A7") (class "Default")
      (node (ref "MCU") (pin "6") (pinfunction "(ADC7/TDI/A7*)PF7_6") (pintype "bidirectional"))
    )
    (net (code "11") (name "AGND") (class "Default")
      (node (ref "ANALOG_BR") (pin "P$2") (pinfunction "P$2_P$2") (pintype "bidirectional"))
      (node (ref "C100") (pin "2") (pinfunction "2_2") (pintype "passive"))
      (node (ref "C122") (pin "2") (pinfunction "2_2") (pintype "passive"))
      (node (ref "C134") (pin "2") (pinfunction "2_2") (pintype "passive"))
      (node (ref "C135") (pin "2") (pinfunction "2_2") (pintype "passive"))
      (node (ref "C136") (pin "2") (pinfunction "2_2") (pintype "passive"))
      (node (ref "C30") (pin "2") (pinfunction "2_2") (pintype "passive"))
      (node (ref "C31") (pin "2") (pinfunction "2_2") (pintype "passive"))
      (node (ref "C32") (pin "2") (pinfunction "2_2") (pintype "passive"))
      (node (ref "C33") (pin "2") (pinfunction "2_2") (pintype "passive"))
      (node (ref "C34") (pin "2") (pinfunction "2_2") (pintype "passive"))
      (node (ref "C47") (pin "2") (pinfunction "2_2") (pintype "passive"))
      (node (ref "C48") (pin "2") (pinfunction "2_2") (pintype "passive"))
      (node (ref "C49") (pin "2") (pinfunction "2_2") (pintype "passive"))
      (node (ref "C50") (pin "2") (pinfunction "2_2") (pintype "passive"))
      (node (ref "C51") (pin "2") (pinfunction "2_2") (pintype "passive"))
      (node (ref "C97") (pin "2") (pinfunction "2_2") (pintype "passive"))
      (node (ref "DEMUX1") (pin "12") (pinfunction "GND_12") (pintype "passive"))
      (node (ref "DEMUX1") (pin "15") (pinfunction "~{EN}_15") (pintype "passive"))
      (node (ref "MCU") (pin "58") (pinfunction "AVSS_58") (pintype "bidirectional"))
      (node (ref "MCU") (pin "61") (pinfunction "AVSS_61") (pintype "bidirectional"))
      (node (ref "R11") (pin "1") (pinfunction "1_1") (pintype "passive"))
      (node (ref "R34") (pin "1") (pinfunction "1_1") (pintype "passive"))
      (node (ref "R35") (pin "1") (pinfunction "1_1") (pintype "passive"))
      (node (ref "R36") (pin "1") (pinfunction "1_1") (pintype "passive"))
      (node (ref "R37") (pin "1") (pinfunction "1_1") (pintype "passive"))
      (node (ref "R38") (pin "1") (pinfunction "1_1") (pintype "passive"))
      (node (ref "R39") (pin "1") (pinfunction "1_1") (pintype "passive"))
      (node (ref "R42") (pin "1") (pinfunction "1_1") (pintype "passive"))
      (node (ref "R43") (pin "1") (pinfunction "1_1") (pintype "passive"))
      (node (ref "R44") (pin "1") (pinfunction "1_1") (pintype "passive"))
    )
    (net (code "12") (name "AVCC") (class "Default")
      (node (ref "C100") (pin "1") (pinfunction "1_1") (pintype "passive"))
      (node (ref "C122") (pin "1") (pinfunction "1_1") (pintype "passive"))
      (node (ref "C134") (pin "1") (pinfunction "1_1") (pintype "passive"))
      (node (ref "C135") (pin "1") (pinfunction "1_1") (pintype "passive"))
      (node (ref "C136") (pin "1") (pinfunction "1_1") (pintype "passive"))
      (node (ref "C30") (pin "1") (pinfunction "1_1") (pintype "passive"))
      (node (ref "C31") (pin "1") (pinfunction "1_1") (pintype "passive"))
      (node (ref "C32") (pin "1") (pinfunction "1_1") (pintype "passive"))
      (node (ref "C33") (pin "1") (pinfunction "1_1") (pintype "passive"))
      (node (ref "C34") (pin "1") (pinfunction "1_1") (pintype "passive"))
      (node (ref "C47") (pin "1") (pinfunction "1_1") (pintype "passive"))
      (node (ref "C48") (pin "1") (pinfunction "1_1") (pintype "passive"))
      (node (ref "C49") (pin "1") (pinfunction "1_1") (pintype "passive"))
      (node (ref "C50") (pin "1") (pinfunction "1_1") (pintype "passive"))
      (node (ref "C51") (pin "1") (pinfunction "1_1") (pintype "passive"))
      (node (ref "C97") (pin "1") (pinfunction "1_1") (pintype "passive"))
      (node (ref "DEMUX1") (pin "24") (pinfunction "VCC_24") (pintype "passive"))
      (node (ref "FLEX1") (pin "+") (pinfunction "+_+") (pintype "passive"))
      (node (ref "FLEX10") (pin "+") (pinfunction "+_+") (pintype "passive"))
      (node (ref "FLEX2") (pin "+") (pinfunction "+_+") (pintype "passive"))
      (node (ref "FLEX3") (pin "+") (pinfunction "+_+") (pintype "passive"))
      (node (ref "FLEX4") (pin "+") (pinfunction "+_+") (pintype "passive"))
      (node (ref "FLEX5") (pin "+") (pinfunction "+_+") (pintype "passive"))
      (node (ref "FLEX6") (pin "+") (pinfunction "+_+") (pintype "passive"))
      (node (ref "FLEX7") (pin "+") (pinfunction "+_+") (pintype "passive"))
      (node (ref "FLEX8") (pin "+") (pinfunction "+_+") (pintype "passive"))
      (node (ref "FLEX9") (pin "+") (pinfunction "+_+") (pintype "passive"))
      (node (ref "L3") (pin "2") (pinfunction "2_2") (pintype "passive"))
      (node (ref "MCU") (pin "59") (pinfunction "EVDD_59") (pintype "bidirectional"))
      (node (ref "MCU") (pin "62") (pinfunction "AREF_62") (pintype "bidirectional"))
    )
    (net (code "13") (name "C8") (class "Default")
      (node (ref "DEMUX1") (pin "23") (pinfunction "C8_23") (pintype "passive"))
    )
    (net (code "14") (name "C9") (class "Default")
      (node (ref "DEMUX1") (pin "22") (pinfunction "C9_22") (pintype "passive"))
    )
    (net (code "15") (name "C10") (class "Default")
      (node (ref "DEMUX1") (pin "21") (pinfunction "C10_21") (pintype "passive"))
    )
    (net (code "16") (name "C11") (class "Default")
      (node (ref "DEMUX1") (pin "20") (pinfunction "C11_20") (pintype "passive"))
    )
    (net (code "17") (name "C12") (class "Default")
      (node (ref "DEMUX1") (pin "19") (pinfunction "C12_19") (pintype "passive"))
    )
    (net (code "18") (name "C13") (class "Default")
      (node (ref "DEMUX1") (pin "18") (pinfunction "C13_18") (pintype "passive"))
    )
    (net (code "19") (name "GND") (class "Default")
      (node (ref "AVR_ISP") (pin "6") (pinfunction "6_6") (pintype "passive"))
      (node (ref "B2") (pin "5") (pinfunction "GND_5") (pintype "bidirectional"))
      (node (ref "BATT2") (pin "-") (pinfunction "N_-") (pintype "bidirectional"))
      (node (ref "C106") (pin "2") (pinfunction "2_2") (pintype "passive"))
      (node (ref "C107") (pin "2") (pinfunction "2_2") (pintype "passive"))
      (node (ref "C108") (pin "2") (pinfunction "2_2") (pintype "passive"))
      (node (ref "C109") (pin "2") (pinfunction "2_2") (pintype "passive"))
      (node (ref "C110") (pin "2") (pinfunction "2_2") (pintype "passive"))
      (node (ref "C111") (pin "2") (pinfunction "2_2") (pintype "passive"))
      (node (ref "C112") (pin "2") (pinfunction "2_2") (pintype "passive"))
      (node (ref "C113") (pin "2") (pinfunction "2_2") (pintype "passive"))
      (node (ref "C114") (pin "2") (pinfunction "2_2") (pintype "passive"))
      (node (ref "C115") (pin "2") (pinfunction "2_2") (pintype "passive"))
      (node (ref "C116") (pin "2") (pinfunction "2_2") (pintype "passive"))
      (node (ref "C118") (pin "2") (pinfunction "2_2") (pintype "passive"))
      (node (ref "C119") (pin "2") (pinfunction "2_2") (pintype "passive"))
      (node (ref "C12") (pin "2") (pinfunction "2_2") (pintype "passive"))
      (node (ref "C120") (pin "2") (pinfunction "2_2") (pintype "passive"))
      (node (ref "C123") (pin "2") (pinfunction "2_2") (pintype "passive"))
      (node (ref "C124") (pin "2") (pinfunction "2_2") (pintype "passive"))
      (node (ref "C126") (pin "2") (pinfunction "2_2") (pintype "passive"))
      (node (ref "C127") (pin "2") (pinfunction "2_2") (pintype "passive"))
      (node (ref "C132") (pin "2") (pinfunction "2_2") (pintype "passive"))
      (node (ref "C16") (pin "2") (pinfunction "2_2") (pintype "passive"))
      (node (ref "C2") (pin "2") (pinfunction "2_2") (pintype "passive"))
      (node (ref "C20") (pin "2") (pinfunction "2_2") (pintype "passive"))
      (node (ref "C25") (pin "2") (pinfunction "2_2") (pintype "passive"))
      (node (ref "C37") (pin "2") (pinfunction "2_2") (pintype "passive"))
      (node (ref "C38") (pin "2") (pinfunction "2_2") (pintype "passive"))
      (node (ref "C44") (pin "2") (pinfunction "2_2") (pintype "passive"))
      (node (ref "C45") (pin "2") (pinfunction "2_2") (pintype "passive"))
      (node (ref "C46") (pin "2") (pinfunction "2_2") (pintype "passive"))
      (node (ref "C8") (pin "2") (pinfunction "2_2") (pintype "passive"))
      (node (ref "C98") (pin "2") (pinfunction "2_2") (pintype "passive"))
      (node (ref "C99") (pin "2") (pinfunction "2_2") (pintype "passive"))
      (node (ref "JP2") (pin "GND") (pinfunction "6_GND") (pintype "passive"))
      (node (ref "L4") (pin "1") (pinfunction "1_1") (pintype "passive"))
      (node (ref "MCU") (pin "10") (pinfunction "AVSS_RFN_10") (pintype "bidirectional"))
      (node (ref "MCU") (pin "11") (pinfunction "TST_11") (pintype "bidirectional"))
      (node (ref "MCU") (pin "20") (pinfunction "DVSS_20") (pintype "bidirectional"))
      (node (ref "MCU") (pin "24") (pinfunction "DVSS_24") (pintype "bidirectional"))
      (node (ref "MCU") (pin "33") (pinfunction "CLKI_33") (pintype "bidirectional"))
      (node (ref "MCU") (pin "35") (pinfunction "DVSS_35") (pintype "bidirectional"))
      (node (ref "MCU") (pin "45") (pinfunction "DVSS_45") (pintype "bidirectional"))
      (node (ref "MCU") (pin "55") (pinfunction "DVSS_55") (pintype "bidirectional"))
      (node (ref "MCU") (pin "7") (pinfunction "AVSS_RFP_7") (pintype "bidirectional"))
      (node (ref "NOISE_BR") (pin "P$2") (pinfunction "P$2_P$2") (pintype "bidirectional"))
      (node (ref "PWM_DRIVER1") (pin "1") (pinfunction "A0_1") (pintype "passive"))
      (node (ref "PWM_DRIVER1") (pin "14") (pinfunction "GND_14") (pintype "passive"))
      (node (ref "PWM_DRIVER1") (pin "2") (pinfunction "A1_2") (pintype "passive"))
      (node (ref "PWM_DRIVER1") (pin "23") (pinfunction "~{OE}_23") (pintype "passive"))
      (node (ref "PWM_DRIVER1") (pin "24") (pinfunction "A5_24") (pintype "passive"))
      (node (ref "PWM_DRIVER1") (pin "25") (pinfunction "EXTCLK_25") (pintype "passive"))
      (node (ref "PWM_DRIVER1") (pin "3") (pinfunction "A2_3") (pintype "passive"))
      (node (ref "PWM_DRIVER1") (pin "4") (pinfunction "A3_4") (pintype "passive"))
      (node (ref "PWM_DRIVER1") (pin "5") (pinfunction "A4_5") (pintype "passive"))
      (node (ref "R14") (pin "1") (pinfunction "1_1") (pintype "passive"))
      (node (ref "R16") (pin "1") (pinfunction "1_1") (pintype "passive"))
      (node (ref "R18") (pin "1") (pinfunction "1_1") (pintype "passive"))
      (node (ref "R20") (pin "1") (pinfunction "1_1") (pintype "passive"))
      (node (ref "R22") (pin "1") (pinfunction "1_1") (pintype "passive"))
      (node (ref "R24") (pin "1") (pinfunction "1_1") (pintype "passive"))
      (node (ref "R26") (pin "1") (pinfunction "1_1") (pintype "passive"))
      (node (ref "R28") (pin "1") (pinfunction "1_1") (pintype "passive"))
      (node (ref "R30") (pin "1") (pinfunction "1_1") (pintype "passive"))
      (node (ref "R32") (pin "1") (pinfunction "1_1") (pintype "passive"))
      (node (ref "R47") (pin "1") (pinfunction "1_1") (pintype "passive"))
      (node (ref "R48") (pin "1") (pinfunction "1_1") (pintype "passive"))
      (node (ref "R49") (pin "1") (pinfunction "1_1") (pintype "passive"))
      (node (ref "VREG1") (pin "1") (pinfunction "GND_1") (pintype "bidirectional"))
      (node (ref "VREG1") (pin "2") (pinfunction "~{EN}_2") (pintype "bidirectional"))
    )
    (net (code "20") (name "MISO") (class "Default")
      (node (ref "AVR_ISP") (pin "1") (pinfunction "1_1") (pintype "passive"))
      (node (ref "MCU") (pin "39") (pinfunction "(PDO/PCINT3/MISO/D12)PB3_39") (pintype "bidirectional"))
    )
    (net (code "21") (name "MOSI") (class "Default")
      (node (ref "AVR_ISP") (pin "4") (pinfunction "4_4") (pintype "passive"))
      (node (ref "MCU") (pin "38") (pinfunction "(PDI/PCINT2/MOSI/D11)PB2_38") (pintype "bidirectional"))
    )
    (net (code "22") (name "NGND") (class "Default")
      (node (ref "C10") (pin "2") (pinfunction "2_2") (pintype "passive"))
      (node (ref "C13") (pin "2") (pinfunction "2_2") (pintype "passive"))
      (node (ref "C14") (pin "2") (pinfunction "2_2") (pintype "passive"))
      (node (ref "C17") (pin "2") (pinfunction "2_2") (pintype "passive"))
      (node (ref "C18") (pin "2") (pinfunction "2_2") (pintype "passive"))
      (node (ref "C21") (pin "2") (pinfunction "2_2") (pintype "passive"))
      (node (ref "C22") (pin "2") (pinfunction "2_2") (pintype "passive"))
      (node (ref "C26") (pin "2") (pinfunction "2_2") (pintype "passive"))
      (node (ref "C27") (pin "2") (pinfunction "2_2") (pintype "passive"))
      (node (ref "C36") (pin "2") (pinfunction "2_2") (pintype "passive"))
      (node (ref "C39") (pin "2") (pinfunction "2_2") (pintype "passive"))
      (node (ref "C40") (pin "2") (pinfunction "2_2") (pintype "passive"))
      (node (ref "C41") (pin "2") (pinfunction "2_2") (pintype "passive"))
      (node (ref "C42") (pin "2") (pinfunction "2_2") (pintype "passive"))
      (node (ref "C43") (pin "2") (pinfunction "2_2") (pintype "passive"))
      (node (ref "C9") (pin "2") (pinfunction "2_2") (pintype "passive"))
      (node (ref "HBRIDGE1") (pin "4") (pinfunction "GND_4") (pintype "passive"))
      (node (ref "HBRIDGE1") (pin "GND") (pinfunction "GND_GND") (pintype "passive"))
      (node (ref "HBRIDGE1") (pin "P$1") (pinfunction "GND_P$1") (pintype "passive"))
      (node (ref "HBRIDGE1") (pin "P$2") (pinfunction "GND_P$2") (pintype "passive"))
      (node (ref "HBRIDGE2") (pin "4") (pinfunction "GND_4") (pintype "passive"))
      (node (ref "HBRIDGE2") (pin "GND") (pinfunction "GND_GND") (pintype "passive"))
      (node (ref "HBRIDGE2") (pin "P$1") (pinfunction "GND_P$1") (pintype "passive"))
      (node (ref "HBRIDGE2") (pin "P$2") (pinfunction "GND_P$2") (pintype "passive"))
      (node (ref "HBRIDGE3") (pin "4") (pinfunction "GND_4") (pintype "passive"))
      (node (ref "HBRIDGE3") (pin "GND") (pinfunction "GND_GND") (pintype "passive"))
      (node (ref "HBRIDGE3") (pin "P$1") (pinfunction "GND_P$1") (pintype "passive"))
      (node (ref "HBRIDGE3") (pin "P$2") (pinfunction "GND_P$2") (pintype "passive"))
      (node (ref "HBRIDGE4") (pin "4") (pinfunction "GND_4") (pintype "passive"))
      (node (ref "HBRIDGE4") (pin "GND") (pinfunction "GND_GND") (pintype "passive"))
      (node (ref "HBRIDGE4") (pin "P$1") (pinfunction "GND_P$1") (pintype "passive"))
      (node (ref "HBRIDGE4") (pin "P$2") (pinfunction "GND_P$2") (pintype "passive"))
      (node (ref "HBRIDGE5") (pin "4") (pinfunction "GND_4") (pintype "passive"))
      (node (ref "HBRIDGE5") (pin "GND") (pinfunction "GND_GND") (pintype "passive"))
      (node (ref "HBRIDGE5") (pin "P$1") (pinfunction "GND_P$1") (pintype "passive"))
      (node (ref "HBRIDGE5") (pin "P$2") (pinfunction "GND_P$2") (pintype "passive"))
      (node (ref "NOISE_BR") (pin "P$1") (pinfunction "P$1_P$1") (pintype "bidirectional"))
      (node (ref "Q1") (pin "2") (pinfunction "S_2") (pintype "passive"))
      (node (ref "Q2") (pin "2") (pinfunction "S_2") (pintype "passive"))
      (node (ref "Q3") (pin "2") (pinfunction "S_2") (pintype "passive"))
      (node (ref "Q4") (pin "2") (pinfunction "S_2") (pintype "passive"))
      (node (ref "Q5") (pin "2") (pinfunction "S_2") (pintype "passive"))
      (node (ref "Q6") (pin "2") (pinfunction "S_2") (pintype "passive"))
      (node (ref "R1") (pin "1") (pinfunction "1_1") (pintype "passive"))
      (node (ref "R12") (pin "1") (pinfunction "1_1") (pintype "passive"))
      (node (ref "R2") (pin "1") (pinfunction "1_1") (pintype "passive"))
      (node (ref "R3") (pin "1") (pinfunction "1_1") (pintype "passive"))
      (node (ref "R4") (pin "1") (pinfunction "1_1") (pintype "passive"))
      (node (ref "R5") (pin "1") (pinfunction "1_1") (pintype "passive"))
      (node (ref "VREG6") (pin "2") (pinfunction "GND_2") (pintype "bidirectional"))
      (node (ref "VREG6") (pin "TAB") (pinfunction "GND_TAB") (pintype "bidirectional"))
      (node (ref "VREG7") (pin "3") (pinfunction "GND_3") (pintype "bidirectional"))
      (node (ref "VREG7") (pin "TAB") (pinfunction "GND_TAB") (pintype "bidirectional"))
    )
    (net (code "23") (name "Net-(A6-SIGNAL)") (class "Default")
      (node (ref "A6") (pin "FEED") (pinfunction "SIGNAL_FEED") (pintype "bidirectional"))
      (node (ref "B2") (pin "1") (pinfunction "IN_1") (pintype "bidirectional"))
      (node (ref "C115") (pin "1") (pinfunction "1_1") (pintype "passive"))
    )
    (net (code "24") (name "Net-(ANALOG_BR-PadP$1)") (class "Default")
      (node (ref "ANALOG_BR") (pin "P$1") (pinfunction "P$1_P$1") (pintype "bidirectional"))
      (node (ref "L4") (pin "2") (pinfunction "2_2") (pintype "passive"))
    )
    (net (code "25") (name "Net-(B2-GND-Pad2)") (class "Default")
      (node (ref "B2") (pin "2") (pinfunction "GND_2") (pintype "bidirectional"))
      (node (ref "C114") (pin "1") (pinfunction "1_1") (pintype "passive"))
    )
    (net (code "26") (name "Net-(B2-OUT1)") (class "Default")
      (node (ref "B2") (pin "4") (pinfunction "OUT1_4") (pintype "bidirectional"))
      (node (ref "MCU") (pin "8") (pinfunction "RFP_8") (pintype "bidirectional"))
    )
    (net (code "27") (name "Net-(B2-OUT2)") (class "Default")
      (node (ref "B2") (pin "3") (pinfunction "OUT2_3") (pintype "bidirectional"))
      (node (ref "MCU") (pin "9") (pinfunction "RFN_9") (pintype "bidirectional"))
    )
    (net (code "28") (name "Net-(BATT2-P)") (class "Default")
      (node (ref "BATT2") (pin "+") (pinfunction "P_+") (pintype "bidirectional"))
      (node (ref "SW1") (pin "P") (pinfunction "1_P") (pintype "passive"))
    )
    (net (code "29") (name "Net-(C132-Pad1)") (class "Default")
      (node (ref "C132") (pin "1") (pinfunction "1_1") (pintype "passive"))
      (node (ref "MCU") (pin "21") (pinfunction "DVDD_21") (pintype "bidirectional"))
      (node (ref "MCU") (pin "22") (pinfunction "DVDD_22") (pintype "bidirectional"))
    )
    (net (code "30") (name "Net-(HBRIDGE1-IN1)") (class "Default")
      (node (ref "HBRIDGE1") (pin "6") (pinfunction "IN1_6") (pintype "passive"))
      (node (ref "R28") (pin "2") (pinfunction "2_2") (pintype "passive"))
      (node (ref "R29") (pin "2") (pinfunction "2_2") (pintype "passive"))
    )
    (net (code "31") (name "Net-(HBRIDGE1-IN2)") (class "Default")
      (node (ref "HBRIDGE1") (pin "5") (pinfunction "IN2_5") (pintype "passive"))
      (node (ref "R26") (pin "2") (pinfunction "2_2") (pintype "passive"))
      (node (ref "R27") (pin "2") (pinfunction "2_2") (pintype "passive"))
    )
    (net (code "32") (name "Net-(HBRIDGE1-OUT1)") (class "Default")
      (node (ref "HBRIDGE1") (pin "2") (pinfunction "OUT1_2") (pintype "passive"))
      (node (ref "TEC1") (pin "COLD") (pinfunction "COLD_COLD") (pintype "passive"))
    )
    (net (code "33") (name "Net-(HBRIDGE1-OUT2)") (class "Default")
      (node (ref "HBRIDGE1") (pin "3") (pinfunction "OUT2_3") (pintype "passive"))
      (node (ref "TEC1") (pin "HOT") (pinfunction "HOT_HOT") (pintype "passive"))
    )
    (net (code "34") (name "Net-(HBRIDGE2-IN1)") (class "Default")
      (node (ref "HBRIDGE2") (pin "6") (pinfunction "IN1_6") (pintype "passive"))
      (node (ref "R24") (pin "2") (pinfunction "2_2") (pintype "passive"))
      (node (ref "R25") (pin "2") (pinfunction "2_2") (pintype "passive"))
    )
    (net (code "35") (name "Net-(HBRIDGE2-IN2)") (class "Default")
      (node (ref "HBRIDGE2") (pin "5") (pinfunction "IN2_5") (pintype "passive"))
      (node (ref "R22") (pin "2") (pinfunction "2_2") (pintype "passive"))
      (node (ref "R23") (pin "2") (pinfunction "2_2") (pintype "passive"))
    )
    (net (code "36") (name "Net-(HBRIDGE2-OUT1)") (class "Default")
      (node (ref "HBRIDGE2") (pin "2") (pinfunction "OUT1_2") (pintype "passive"))
      (node (ref "TEC2") (pin "COLD") (pinfunction "COLD_COLD") (pintype "passive"))
    )
    (net (code "37") (name "Net-(HBRIDGE2-OUT2)") (class "Default")
      (node (ref "HBRIDGE2") (pin "3") (pinfunction "OUT2_3") (pintype "passive"))
      (node (ref "TEC2") (pin "HOT") (pinfunction "HOT_HOT") (pintype "passive"))
    )
    (net (code "38") (name "Net-(HBRIDGE3-IN1)") (class "Default")
      (node (ref "HBRIDGE3") (pin "6") (pinfunction "IN1_6") (pintype "passive"))
      (node (ref "R20") (pin "2") (pinfunction "2_2") (pintype "passive"))
      (node (ref "R21") (pin "2") (pinfunction "2_2") (pintype "passive"))
    )
    (net (code "39") (name "Net-(HBRIDGE3-IN2)") (class "Default")
      (node (ref "HBRIDGE3") (pin "5") (pinfunction "IN2_5") (pintype "passive"))
      (node (ref "R18") (pin "2") (pinfunction "2_2") (pintype "passive"))
      (node (ref "R19") (pin "2") (pinfunction "2_2") (pintype "passive"))
    )
    (net (code "40") (name "Net-(HBRIDGE3-OUT1)") (class "Default")
      (node (ref "HBRIDGE3") (pin "2") (pinfunction "OUT1_2") (pintype "passive"))
      (node (ref "TEC3") (pin "COLD") (pinfunction "COLD_COLD") (pintype "passive"))
    )
    (net (code "41") (name "Net-(HBRIDGE3-OUT2)") (class "Default")
      (node (ref "HBRIDGE3") (pin "3") (pinfunction "OUT2_3") (pintype "passive"))
      (node (ref "TEC3") (pin "HOT") (pinfunction "HOT_HOT") (pintype "passive"))
    )
    (net (code "42") (name "Net-(HBRIDGE4-IN1)") (class "Default")
      (node (ref "HBRIDGE4") (pin "6") (pinfunction "IN1_6") (pintype "passive"))
      (node (ref "R16") (pin "2") (pinfunction "2_2") (pintype "passive"))
      (node (ref "R17") (pin "2") (pinfunction "2_2") (pintype "passive"))
    )
    (net (code "43") (name "Net-(HBRIDGE4-IN2)") (class "Default")
      (node (ref "HBRIDGE4") (pin "5") (pinfunction "IN2_5") (pintype "passive"))
      (node (ref "R14") (pin "2") (pinfunction "2_2") (pintype "passive"))
      (node (ref "R15") (pin "2") (pinfunction "2_2") (pintype "passive"))
    )
    (net (code "44") (name "Net-(HBRIDGE4-OUT1)") (class "Default")
      (node (ref "HBRIDGE4") (pin "2") (pinfunction "OUT1_2") (pintype "passive"))
      (node (ref "TEC4") (pin "COLD") (pinfunction "COLD_COLD") (pintype "passive"))
    )
    (net (code "45") (name "Net-(HBRIDGE4-OUT2)") (class "Default")
      (node (ref "HBRIDGE4") (pin "3") (pinfunction "OUT2_3") (pintype "passive"))
      (node (ref "TEC4") (pin "HOT") (pinfunction "HOT_HOT") (pintype "passive"))
    )
    (net (code "46") (name "Net-(HBRIDGE5-IN1)") (class "Default")
      (node (ref "HBRIDGE5") (pin "6") (pinfunction "IN1_6") (pintype "passive"))
      (node (ref "R32") (pin "2") (pinfunction "2_2") (pintype "passive"))
      (node (ref "R33") (pin "2") (pinfunction "2_2") (pintype "passive"))
    )
    (net (code "47") (name "Net-(HBRIDGE5-IN2)") (class "Default")
      (node (ref "HBRIDGE5") (pin "5") (pinfunction "IN2_5") (pintype "passive"))
      (node (ref "R30") (pin "2") (pinfunction "2_2") (pintype "passive"))
      (node (ref "R31") (pin "2") (pinfunction "2_2") (pintype "passive"))
    )
    (net (code "48") (name "Net-(HBRIDGE5-OUT1)") (class "Default")
      (node (ref "HBRIDGE5") (pin "2") (pinfunction "OUT1_2") (pintype "passive"))
      (node (ref "TEC5") (pin "COLD") (pinfunction "COLD_COLD") (pintype "passive"))
    )
    (net (code "49") (name "Net-(HBRIDGE5-OUT2)") (class "Default")
      (node (ref "HBRIDGE5") (pin "3") (pinfunction "OUT2_3") (pintype "passive"))
      (node (ref "TEC5") (pin "HOT") (pinfunction "HOT_HOT") (pintype "passive"))
    )
    (net (code "50") (name "Net-(JP2-2)") (class "Default")
      (node (ref "C117") (pin "1") (pinfunction "1_1") (pintype "passive"))
      (node (ref "JP2") (pin "DTR") (pinfunction "2_DTR") (pintype "passive"))
    )
    (net (code "51") (name "Net-(LED1-PadK)") (class "Default")
      (node (ref "LED1") (pin "K") (pinfunction "K_K") (pintype "passive"))
      (node (ref "R49") (pin "2") (pinfunction "2_2") (pintype "passive"))
    )
    (net (code "52") (name "Net-(LED2-PadK)") (class "Default")
      (node (ref "LED2") (pin "K") (pinfunction "K_K") (pintype "passive"))
      (node (ref "R48") (pin "2") (pinfunction "2_2") (pintype "passive"))
    )
    (net (code "53") (name "Net-(LED3-PadK)") (class "Default")
      (node (ref "LED3") (pin "K") (pinfunction "K_K") (pintype "passive"))
      (node (ref "R47") (pin "2") (pinfunction "2_2") (pintype "passive"))
    )
    (net (code "54") (name "Net-(MCU-AVDD)") (class "Default")
      (node (ref "C110") (pin "1") (pinfunction "1_1") (pintype "passive"))
      (node (ref "MCU") (pin "60") (pinfunction "AVDD_60") (pintype "bidirectional"))
    )
    (net (code "55") (name "Net-(MCU-XTAL1)") (class "Default")
      (node (ref "C113") (pin "1") (pinfunction "1_1") (pintype "passive"))
      (node (ref "MCU") (pin "57") (pinfunction "XTAL1_57") (pintype "bidirectional"))
      (node (ref "Y2") (pin "3") (pinfunction "2_3") (pintype "passive"))
    )
    (net (code "56") (name "Net-(MCU-XTAL2)") (class "Default")
      (node (ref "C112") (pin "1") (pinfunction "1_1") (pintype "passive"))
      (node (ref "MCU") (pin "56") (pinfunction "XTAL2_56") (pintype "bidirectional"))
      (node (ref "Y2") (pin "1") (pinfunction "1_1") (pintype "passive"))
    )
    (net (code "57") (name "Net-(Q1-D)") (class "Default")
      (node (ref "C3") (pin "2") (pinfunction "2_2") (pintype "passive"))
      (node (ref "D1") (pin "A") (pinfunction "A_A") (pintype "passive"))
      (node (ref "Q1") (pin "3") (pinfunction "D_3") (pintype "passive"))
      (node (ref "VIBE1") (pin "2") (pinfunction "-_2") (pintype "passive"))
    )
    (net (code "58") (name "Net-(Q1-G)") (class "Default")
      (node (ref "Q1") (pin "1") (pinfunction "G_1") (pintype "passive"))
      (node (ref "R1") (pin "2") (pinfunction "2_2") (pintype "passive"))
      (node (ref "R6") (pin "2") (pinfunction "2_2") (pintype "passive"))
    )
    (net (code "59") (name "Net-(Q2-D)") (class "Default")
      (node (ref "C4") (pin "2") (pinfunction "2_2") (pintype "passive"))
      (node (ref "D2") (pin "A") (pinfunction "A_A") (pintype "passive"))
      (node (ref "Q2") (pin "3") (pinfunction "D_3") (pintype "passive"))
      (node (ref "VIBE2") (pin "2") (pinfunction "-_2") (pintype "passive"))
    )
    (net (code "60") (name "Net-(Q2-G)") (class "Default")
      (node (ref "Q2") (pin "1") (pinfunction "G_1") (pintype "passive"))
      (node (ref "R2") (pin "2") (pinfunction "2_2") (pintype "passive"))
      (node (ref "R7") (pin "2") (pinfunction "2_2") (pintype "passive"))
    )
    (net (code "61") (name "Net-(Q3-D)") (class "Default")
      (node (ref "C5") (pin "2") (pinfunction "2_2") (pintype "passive"))
      (node (ref "D3") (pin "A") (pinfunction "A_A") (pintype "passive"))
      (node (ref "Q3") (pin "3") (pinfunction "D_3") (pintype "passive"))
      (node (ref "VIBE3") (pin "2") (pinfunction "-_2") (pintype "passive"))
    )
    (net (code "62") (name "Net-(Q3-G)") (class "Default")
      (node (ref "Q3") (pin "1") (pinfunction "G_1") (pintype "passive"))
      (node (ref "R3") (pin "2") (pinfunction "2_2") (pintype "passive"))
      (node (ref "R8") (pin "2") (pinfunction "2_2") (pintype "passive"))
    )
    (net (code "63") (name "Net-(Q4-D)") (class "Default")
      (node (ref "C6") (pin "2") (pinfunction "2_2") (pintype "passive"))
      (node (ref "D4") (pin "A") (pinfunction "A_A") (pintype "passive"))
      (node (ref "Q4") (pin "3") (pinfunction "D_3") (pintype "passive"))
      (node (ref "VIBE4") (pin "2") (pinfunction "-_2") (pintype "passive"))
    )
    (net (code "64") (name "Net-(Q4-G)") (class "Default")
      (node (ref "Q4") (pin "1") (pinfunction "G_1") (pintype "passive"))
      (node (ref "R4") (pin "2") (pinfunction "2_2") (pintype "passive"))
      (node (ref "R9") (pin "2") (pinfunction "2_2") (pintype "passive"))
    )
    (net (code "65") (name "Net-(Q5-D)") (class "Default")
      (node (ref "C7") (pin "2") (pinfunction "2_2") (pintype "passive"))
      (node (ref "D5") (pin "A") (pinfunction "A_A") (pintype "passive"))
      (node (ref "Q5") (pin "3") (pinfunction "D_3") (pintype "passive"))
      (node (ref "VIBE5") (pin "2") (pinfunction "-_2") (pintype "passive"))
    )
    (net (code "66") (name "Net-(Q5-G)") (class "Default")
      (node (ref "Q5") (pin "1") (pinfunction "G_1") (pintype "passive"))
      (node (ref "R10") (pin "2") (pinfunction "2_2") (pintype "passive"))
      (node (ref "R5") (pin "2") (pinfunction "2_2") (pintype "passive"))
    )
    (net (code "67") (name "Net-(Q6-D)") (class "Default")
      (node (ref "C1") (pin "2") (pinfunction "2_2") (pintype "passive"))
      (node (ref "D12") (pin "A") (pinfunction "A_A") (pintype "passive"))
      (node (ref "Q6") (pin "3") (pinfunction "D_3") (pintype "passive"))
      (node (ref "VIBE6") (pin "2") (pinfunction "-_2") (pintype "passive"))
    )
    (net (code "68") (name "Net-(Q6-G)") (class "Default")
      (node (ref "Q6") (pin "1") (pinfunction "G_1") (pintype "passive"))
      (node (ref "R12") (pin "2") (pinfunction "2_2") (pintype "passive"))
      (node (ref "R13") (pin "2") (pinfunction "2_2") (pintype "passive"))
    )
    (net (code "69") (name "PB4") (class "Default")
      (node (ref "MCU") (pin "40") (pinfunction "(PCINT4/OC2A/D9-PWM9)PB4_40") (pintype "bidirectional"))
    )
    (net (code "70") (name "PB5") (class "Default")
      (node (ref "MCU") (pin "41") (pinfunction "(PCINT5/OC1A/D8-PWM8)PB5_41") (pintype "bidirectional"))
    )
    (net (code "71") (name "PB6") (class "Default")
      (node (ref "LED2") (pin "A") (pinfunction "A_A") (pintype "passive"))
      (node (ref "MCU") (pin "42") (pinfunction "(PCINT6/OC1B/D34-PWM34)PB6_42") (pintype "bidirectional"))
    )
    (net (code "72") (name "PB7") (class "Default")
      (node (ref "LED1") (pin "A") (pinfunction "A_A") (pintype "passive"))
      (node (ref "MCU") (pin "43") (pinfunction "(PCINT7/OC0A/OC1C/D35-PWM35)PB7_43") (pintype "bidirectional"))
    )
    (net (code "73") (name "PD4") (class "Default")
      (node (ref "DEMUX1") (pin "13") (pinfunction "S3_13") (pintype "passive"))
      (node (ref "MCU") (pin "29") (pinfunction "(ICP1/D22)PD4_29") (pintype "bidirectional"))
    )
    (net (code "74") (name "PD5") (class "Default")
      (node (ref "DEMUX1") (pin "14") (pinfunction "S2_14") (pintype "passive"))
      (node (ref "MCU") (pin "30") (pinfunction "(XCK1/D23)PD5_30") (pintype "bidirectional"))
    )
    (net (code "75") (name "PD6") (class "Default")
      (node (ref "DEMUX1") (pin "11") (pinfunction "S1_11") (pintype "passive"))
      (node (ref "MCU") (pin "31") (pinfunction "(T1/D24)PD6_31") (pintype "bidirectional"))
    )
    (net (code "76") (name "PD7") (class "Default")
      (node (ref "DEMUX1") (pin "10") (pinfunction "S0_10") (pintype "passive"))
      (node (ref "MCU") (pin "32") (pinfunction "(T0/D25)PD7_32") (pintype "bidirectional"))
    )
    (net (code "77") (name "PE2") (class "Default")
      (node (ref "MCU") (pin "48") (pinfunction "(XCK0/AIN0/D2)PE2_48") (pintype "bidirectional"))
    )
    (net (code "78") (name "PE3") (class "Default")
      (node (ref "MCU") (pin "49") (pinfunction "(AIN1/OC3A/D3-PWM3)PE3_49") (pintype "bidirectional"))
    )
    (net (code "79") (name "PE4") (class "Default")
      (node (ref "MCU") (pin "50") (pinfunction "(INT4/OC3B/D4-PWM4)PE4_50") (pintype "bidirectional"))
    )
    (net (code "80") (name "PE5") (class "Default")
      (node (ref "MCU") (pin "51") (pinfunction "(INT5/OC3C/D5-PWM5)PE5_51") (pintype "bidirectional"))
    )
    (net (code "81") (name "PE6") (class "Default")
      (node (ref "MCU") (pin "52") (pinfunction "(T3/INT6/D6)PE6_52") (pintype "bidirectional"))
    )
    (net (code "82") (name "PE7") (class "Default")
      (node (ref "MCU") (pin "53") (pinfunction "(ICP3/INT7/CLKO/D7)PE7_53") (pintype "bidirectional"))
    )
    (net (code "83") (name "PG0") (class "Default")
      (node (ref "MCU") (pin "14") (pinfunction "(DIG3/D16)PG0_14") (pintype "bidirectional"))
    )
    (net (code "84") (name "PG1") (class "Default")
      (node (ref "MCU") (pin "15") (pinfunction "(DIG1/D17)PG1_15") (pintype "bidirectional"))
    )
    (net (code "85") (name "PG2") (class "Default")
      (node (ref "MCU") (pin "16") (pinfunction "(AMR/D18)PG2_16") (pintype "bidirectional"))
    )
    (net (code "86") (name "PG3") (class "Default")
      (node (ref "MCU") (pin "17") (pinfunction "(TOSC2)PG3_17") (pintype "bidirectional"))
    )
    (net (code "87") (name "PG4") (class "Default")
      (node (ref "MCU") (pin "18") (pinfunction "(TOSC1)PG4_18") (pintype "bidirectional"))
    )
    (net (code "88") (name "PG5") (class "Default")
      (node (ref "MCU") (pin "19") (pinfunction "(OC0B/D19-PWM19)PG5_19") (pintype "bidirectional"))
    )
    (net (code "89") (name "RESET") (class "Default")
      (node (ref "AVR_ISP") (pin "5") (pinfunction "5_5") (pintype "passive"))
      (node (ref "C117") (pin "2") (pinfunction "2_2") (pintype "passive"))
      (node (ref "D11") (pin "A") (pinfunction "A_A") (pintype "passive"))
      (node (ref "MCU") (pin "12") (pinfunction "RSTN_12") (pintype "bidirectional"))
      (node (ref "R46") (pin "1") (pinfunction "1_1") (pintype "passive"))
    )
    (net (code "90") (name "RX0") (class "Default")
      (node (ref "JP2") (pin "TXO") (pinfunction "4_TXO") (pintype "passive"))
      (node (ref "MCU") (pin "46") (pinfunction "(PCINT8/RXD0/D0)PE0_46") (pintype "bidirectional"))
    )
    (net (code "91") (name "RX1") (class "Default")
      (node (ref "MCU") (pin "27") (pinfunction "(INT2/RXD1/D20)PD2_27") (pintype "bidirectional"))
    )
    (net (code "92") (name "SCK") (class "Default")
      (node (ref "AVR_ISP") (pin "3") (pinfunction "3_3") (pintype "passive"))
      (node (ref "MCU") (pin "37") (pinfunction "(PCINT1/SCK/D13)PB1_37") (pintype "bidirectional"))
    )
    (net (code "93") (name "SCL") (class "Default")
      (node (ref "MCU") (pin "25") (pinfunction "(INT0/SCL/D15)PD0_25") (pintype "bidirectional"))
      (node (ref "PWM_DRIVER1") (pin "26") (pinfunction "SCL_26") (pintype "passive"))
      (node (ref "R40") (pin "1") (pinfunction "1_1") (pintype "passive"))
    )
    (net (code "94") (name "SDA") (class "Default")
      (node (ref "MCU") (pin "26") (pinfunction "(INT1/SDA/D14)PD1_26") (pintype "bidirectional"))
      (node (ref "PWM_DRIVER1") (pin "27") (pinfunction "SDA_27") (pintype "passive"))
      (node (ref "R41") (pin "1") (pinfunction "1_1") (pintype "passive"))
    )
    (net (code "95") (name "SSN") (class "Default")
      (node (ref "MCU") (pin "36") (pinfunction "(PCINT0/SSN/D10)PB0_36") (pintype "bidirectional"))
    )
    (net (code "96") (name "STRAIN_1") (class "Default")
      (node (ref "DEMUX1") (pin "9") (pinfunction "C0_9") (pintype "passive"))
      (node (ref "FLEX2") (pin "-") (pinfunction "-_-") (pintype "passive"))
      (node (ref "R34") (pin "2") (pinfunction "2_2") (pintype "passive"))
    )
    (net (code "97") (name "STRAIN_2") (class "Default")
      (node (ref "DEMUX1") (pin "8") (pinfunction "C1_8") (pintype "passive"))
      (node (ref "FLEX7") (pin "-") (pinfunction "-_-") (pintype "passive"))
      (node (ref "R39") (pin "2") (pinfunction "2_2") (pintype "passive"))
    )
    (net (code "98") (name "STRAIN_3") (class "Default")
      (node (ref "DEMUX1") (pin "7") (pinfunction "C2_7") (pintype "passive"))
      (node (ref "FLEX3") (pin "-") (pinfunction "-_-") (pintype "passive"))
      (node (ref "R35") (pin "2") (pinfunction "2_2") (pintype "passive"))
    )
    (net (code "99") (name "STRAIN_4") (class "Default")
      (node (ref "DEMUX1") (pin "6") (pinfunction "C3_6") (pintype "passive"))
      (node (ref "FLEX8") (pin "-") (pinfunction "-_-") (pintype "passive"))
      (node (ref "R42") (pin "2") (pinfunction "2_2") (pintype "passive"))
    )
    (net (code "100") (name "STRAIN_5") (class "Default")
      (node (ref "DEMUX1") (pin "5") (pinfunction "C4_5") (pintype "passive"))
      (node (ref "FLEX4") (pin "-") (pinfunction "-_-") (pintype "passive"))
      (node (ref "R36") (pin "2") (pinfunction "2_2") (pintype "passive"))
    )
    (net (code "101") (name "STRAIN_6") (class "Default")
      (node (ref "DEMUX1") (pin "4") (pinfunction "C5_4") (pintype "passive"))
      (node (ref "FLEX9") (pin "-") (pinfunction "-_-") (pintype "passive"))
      (node (ref "R43") (pin "2") (pinfunction "2_2") (pintype "passive"))
    )
    (net (code "102") (name "STRAIN_7") (class "Default")
      (node (ref "DEMUX1") (pin "3") (pinfunction "C6_3") (pintype "passive"))
      (node (ref "FLEX5") (pin "-") (pinfunction "-_-") (pintype "passive"))
      (node (ref "R37") (pin "2") (pinfunction "2_2") (pintype "passive"))
    )
    (net (code "103") (name "STRAIN_8") (class "Default")
      (node (ref "DEMUX1") (pin "2") (pinfunction "C7_2") (pintype "passive"))
      (node (ref "FLEX10") (pin "-") (pinfunction "-_-") (pintype "passive"))
      (node (ref "R44") (pin "2") (pinfunction "2_2") (pintype "passive"))
    )
    (net (code "104") (name "STRAIN_9") (class "Default")
      (node (ref "DEMUX1") (pin "17") (pinfunction "C14_17") (pintype "passive"))
      (node (ref "FLEX1") (pin "-") (pinfunction "-_-") (pintype "passive"))
      (node (ref "R11") (pin "2") (pinfunction "2_2") (pintype "passive"))
    )
    (net (code "105") (name "STRAIN_10") (class "Default")
      (node (ref "DEMUX1") (pin "16") (pinfunction "C15_16") (pintype "passive"))
      (node (ref "FLEX6") (pin "-") (pinfunction "-_-") (pintype "passive"))
      (node (ref "R38") (pin "2") (pinfunction "2_2") (pintype "passive"))
    )
    (net (code "106") (name "TEC_1_COLD") (class "Default")
      (node (ref "PWM_DRIVER1") (pin "12") (pinfunction "PWM6_12") (pintype "passive"))
      (node (ref "R27") (pin "1") (pinfunction "1_1") (pintype "passive"))
    )
    (net (code "107") (name "TEC_1_HOT") (class "Default")
      (node (ref "PWM_DRIVER1") (pin "13") (pinfunction "PWM7_13") (pintype "passive"))
      (node (ref "R29") (pin "1") (pinfunction "1_1") (pintype "passive"))
    )
    (net (code "108") (name "TEC_2_COLD") (class "Default")
      (node (ref "PWM_DRIVER1") (pin "21") (pinfunction "PWM14_21") (pintype "passive"))
      (node (ref "R23") (pin "1") (pinfunction "1_1") (pintype "passive"))
    )
    (net (code "109") (name "TEC_2_HOT") (class "Default")
      (node (ref "PWM_DRIVER1") (pin "22") (pinfunction "PWM15_22") (pintype "passive"))
      (node (ref "R25") (pin "1") (pinfunction "1_1") (pintype "passive"))
    )
    (net (code "110") (name "TEC_3_COLD") (class "Default")
      (node (ref "PWM_DRIVER1") (pin "19") (pinfunction "PWM12_19") (pintype "passive"))
      (node (ref "R19") (pin "1") (pinfunction "1_1") (pintype "passive"))
    )
    (net (code "111") (name "TEC_3_HOT") (class "Default")
      (node (ref "PWM_DRIVER1") (pin "20") (pinfunction "PWM13_20") (pintype "passive"))
      (node (ref "R21") (pin "1") (pinfunction "1_1") (pintype "passive"))
    )
    (net (code "112") (name "TEC_4_COLD") (class "Default")
      (node (ref "PWM_DRIVER1") (pin "17") (pinfunction "PWM10_17") (pintype "passive"))
      (node (ref "R15") (pin "1") (pinfunction "1_1") (pintype "passive"))
    )
    (net (code "113") (name "TEC_4_HOT") (class "Default")
      (node (ref "PWM_DRIVER1") (pin "18") (pinfunction "PWM11_18") (pintype "passive"))
      (node (ref "R17") (pin "1") (pinfunction "1_1") (pintype "passive"))
    )
    (net (code "114") (name "TEC_5_COLD") (class "Default")
      (node (ref "PWM_DRIVER1") (pin "15") (pinfunction "PWM8_15") (pintype "passive"))
      (node (ref "R31") (pin "1") (pinfunction "1_1") (pintype "passive"))
    )
    (net (code "115") (name "TEC_5_HOT") (class "Default")
      (node (ref "PWM_DRIVER1") (pin "16") (pinfunction "PWM9_16") (pintype "passive"))
      (node (ref "R33") (pin "1") (pinfunction "1_1") (pintype "passive"))
    )
    (net (code "116") (name "TX0") (class "Default")
      (node (ref "JP2") (pin "RXI") (pinfunction "3_RXI") (pintype "passive"))
      (node (ref "MCU") (pin "47") (pinfunction "(TXD0/D1)PE1_47") (pintype "bidirectional"))
    )
    (net (code "117") (name "TX1") (class "Default")
      (node (ref "MCU") (pin "28") (pinfunction "(INT3/TXD1/D21)PD3_28") (pintype "bidirectional"))
    )
    (net (code "118") (name "VBATT") (class "Default")
      (node (ref "C118") (pin "1") (pinfunction "1_1") (pintype "passive"))
      (node (ref "C119") (pin "1") (pinfunction "1_1") (pintype "passive"))
      (node (ref "C120") (pin "1") (pinfunction "1_1") (pintype "passive"))
      (node (ref "C126") (pin "1") (pinfunction "1_1") (pintype "passive"))
      (node (ref "C127") (pin "1") (pinfunction "1_1") (pintype "passive"))
      (node (ref "C2") (pin "1") (pinfunction "1_1") (pintype "passive"))
      (node (ref "C37") (pin "1") (pinfunction "1_1") (pintype "passive"))
      (node (ref "C38") (pin "1") (pinfunction "1_1") (pintype "passive"))
      (node (ref "C44") (pin "1") (pinfunction "1_1") (pintype "passive"))
      (node (ref "C45") (pin "1") (pinfunction "1_1") (pintype "passive"))
      (node (ref "C46") (pin "1") (pinfunction "1_1") (pintype "passive"))
      (node (ref "D13") (pin "K") (pinfunction "K_K") (pintype "passive"))
      (node (ref "D14") (pin "K") (pinfunction "K_K") (pintype "passive"))
      (node (ref "D8") (pin "K") (pinfunction "K_K") (pintype "passive"))
      (node (ref "LED3") (pin "A") (pinfunction "A_A") (pintype "passive"))
      (node (ref "SW1") (pin "S1") (pinfunction "2_S1") (pintype "passive"))
      (node (ref "VREG1") (pin "3") (pinfunction "VIN_3") (pintype "bidirectional"))
      (node (ref "VREG1") (pin "4") (pinfunction "VIN_4") (pintype "bidirectional"))
      (node (ref "VREG6") (pin "1") (pinfunction "VI_1") (pintype "bidirectional"))
      (node (ref "VREG7") (pin "1") (pinfunction "~{SHDN}_1") (pintype "bidirectional"))
      (node (ref "VREG7") (pin "2") (pinfunction "VIN_2") (pintype "bidirectional"))
    )
    (net (code "119") (name "VCC") (class "Default")
      (node (ref "AVR_ISP") (pin "2") (pinfunction "2_2") (pintype "passive"))
      (node (ref "C106") (pin "1") (pinfunction "1_1") (pintype "passive"))
      (node (ref "C107") (pin "1") (pinfunction "1_1") (pintype "passive"))
      (node (ref "C108") (pin "1") (pinfunction "1_1") (pintype "passive"))
      (node (ref "C109") (pin "1") (pinfunction "1_1") (pintype "passive"))
      (node (ref "C111") (pin "1") (pinfunction "1_1") (pintype "passive"))
      (node (ref "C116") (pin "1") (pinfunction "1_1") (pintype "passive"))
      (node (ref "C12") (pin "1") (pinfunction "1_1") (pintype "passive"))
      (node (ref "C123") (pin "1") (pinfunction "1_1") (pintype "passive"))
      (node (ref "C124") (pin "1") (pinfunction "1_1") (pintype "passive"))
      (node (ref "C16") (pin "1") (pinfunction "1_1") (pintype "passive"))
      (node (ref "C20") (pin "1") (pinfunction "1_1") (pintype "passive"))
      (node (ref "C25") (pin "1") (pinfunction "1_1") (pintype "passive"))
      (node (ref "C8") (pin "1") (pinfunction "1_1") (pintype "passive"))
      (node (ref "C98") (pin "1") (pinfunction "1_1") (pintype "passive"))
      (node (ref "C99") (pin "1") (pinfunction "1_1") (pintype "passive"))
      (node (ref "D11") (pin "K") (pinfunction "K_K") (pintype "passive"))
      (node (ref "D8") (pin "A") (pinfunction "A_A") (pintype "passive"))
      (node (ref "HBRIDGE1") (pin "7") (pinfunction "NSLEEP_7") (pintype "passive"))
      (node (ref "HBRIDGE1") (pin "8") (pinfunction "VCC_8") (pintype "passive"))
      (node (ref "HBRIDGE2") (pin "7") (pinfunction "NSLEEP_7") (pintype "passive"))
      (node (ref "HBRIDGE2") (pin "8") (pinfunction "VCC_8") (pintype "passive"))
      (node (ref "HBRIDGE3") (pin "7") (pinfunction "NSLEEP_7") (pintype "passive"))
      (node (ref "HBRIDGE3") (pin "8") (pinfunction "VCC_8") (pintype "passive"))
      (node (ref "HBRIDGE4") (pin "7") (pinfunction "NSLEEP_7") (pintype "passive"))
      (node (ref "HBRIDGE4") (pin "8") (pinfunction "VCC_8") (pintype "passive"))
      (node (ref "HBRIDGE5") (pin "7") (pinfunction "NSLEEP_7") (pintype "passive"))
      (node (ref "HBRIDGE5") (pin "8") (pinfunction "VCC_8") (pintype "passive"))
      (node (ref "JP2") (pin "VCC") (pinfunction "1_VCC") (pintype "passive"))
      (node (ref "L3") (pin "1") (pinfunction "1_1") (pintype "passive"))
      (node (ref "MCU") (pin "23") (pinfunction "DEVDD_23") (pintype "bidirectional"))
      (node (ref "MCU") (pin "34") (pinfunction "DEVDD_34") (pintype "bidirectional"))
      (node (ref "MCU") (pin "44") (pinfunction "DEVDD_44") (pintype "bidirectional"))
      (node (ref "MCU") (pin "54") (pinfunction "DEVDD_54") (pintype "bidirectional"))
      (node (ref "PWM_DRIVER1") (pin "28") (pinfunction "VCC_28") (pintype "passive"))
      (node (ref "R40") (pin "2") (pinfunction "2_2") (pintype "passive"))
      (node (ref "R41") (pin "2") (pinfunction "2_2") (pintype "passive"))
      (node (ref "R46") (pin "2") (pinfunction "2_2") (pintype "passive"))
      (node (ref "VREG1") (pin "5") (pinfunction "VOUT_5") (pintype "bidirectional"))
      (node (ref "VREG1") (pin "6") (pinfunction "VOUT_6") (pintype "bidirectional"))
    )
    (net (code "120") (name "VIBE_1") (class "Default")
      (node (ref "PWM_DRIVER1") (pin "6") (pinfunction "PWM0_6") (pintype "passive"))
      (node (ref "R6") (pin "1") (pinfunction "1_1") (pintype "passive"))
    )
    (net (code "121") (name "VIBE_2") (class "Default")
      (node (ref "PWM_DRIVER1") (pin "7") (pinfunction "PWM1_7") (pintype "passive"))
      (node (ref "R7") (pin "1") (pinfunction "1_1") (pintype "passive"))
    )
    (net (code "122") (name "VIBE_3") (class "Default")
      (node (ref "PWM_DRIVER1") (pin "8") (pinfunction "PWM2_8") (pintype "passive"))
      (node (ref "R8") (pin "1") (pinfunction "1_1") (pintype "passive"))
    )
    (net (code "123") (name "VIBE_4") (class "Default")
      (node (ref "PWM_DRIVER1") (pin "9") (pinfunction "PWM3_9") (pintype "passive"))
      (node (ref "R9") (pin "1") (pinfunction "1_1") (pintype "passive"))
    )
    (net (code "124") (name "VIBE_5") (class "Default")
      (node (ref "PWM_DRIVER1") (pin "10") (pinfunction "PWM4_10") (pintype "passive"))
      (node (ref "R10") (pin "1") (pinfunction "1_1") (pintype "passive"))
    )
    (net (code "125") (name "VIBE_6") (class "Default")
      (node (ref "PWM_DRIVER1") (pin "11") (pinfunction "PWM5_11") (pintype "passive"))
      (node (ref "R13") (pin "1") (pinfunction "1_1") (pintype "passive"))
    )
    (net (code "126") (name "unconnected-(JP2-5-PadCTS)") (class "Default")
      (node (ref "JP2") (pin "CTS") (pinfunction "5_CTS") (pintype "passive"))
    )
    (net (code "127") (name "unconnected-(MCU-RSTON-Pad13)") (class "Default")
      (node (ref "MCU") (pin "13") (pinfunction "RSTON_13") (pintype "bidirectional"))
    )
    (net (code "128") (name "unconnected-(SW1-3-PadS2)") (class "Default")
      (node (ref "SW1") (pin "S2") (pinfunction "3_S2") (pintype "passive"))
    )
    (net (code "129") (name "unconnected-(VREG1-FB{slash}NC-Pad7)") (class "Default")
      (node (ref "VREG1") (pin "7") (pinfunction "FB/NC_7") (pintype "bidirectional"))
    )
    (net (code "130") (name "unconnected-(VREG1-PG-Pad8)") (class "Default")
      (node (ref "VREG1") (pin "8") (pinfunction "PG_8") (pintype "bidirectional"))
    )
  )
)
